# nano-esp-stm-breakout.net
KiCad netlist of a schematic drawn in EAGLE
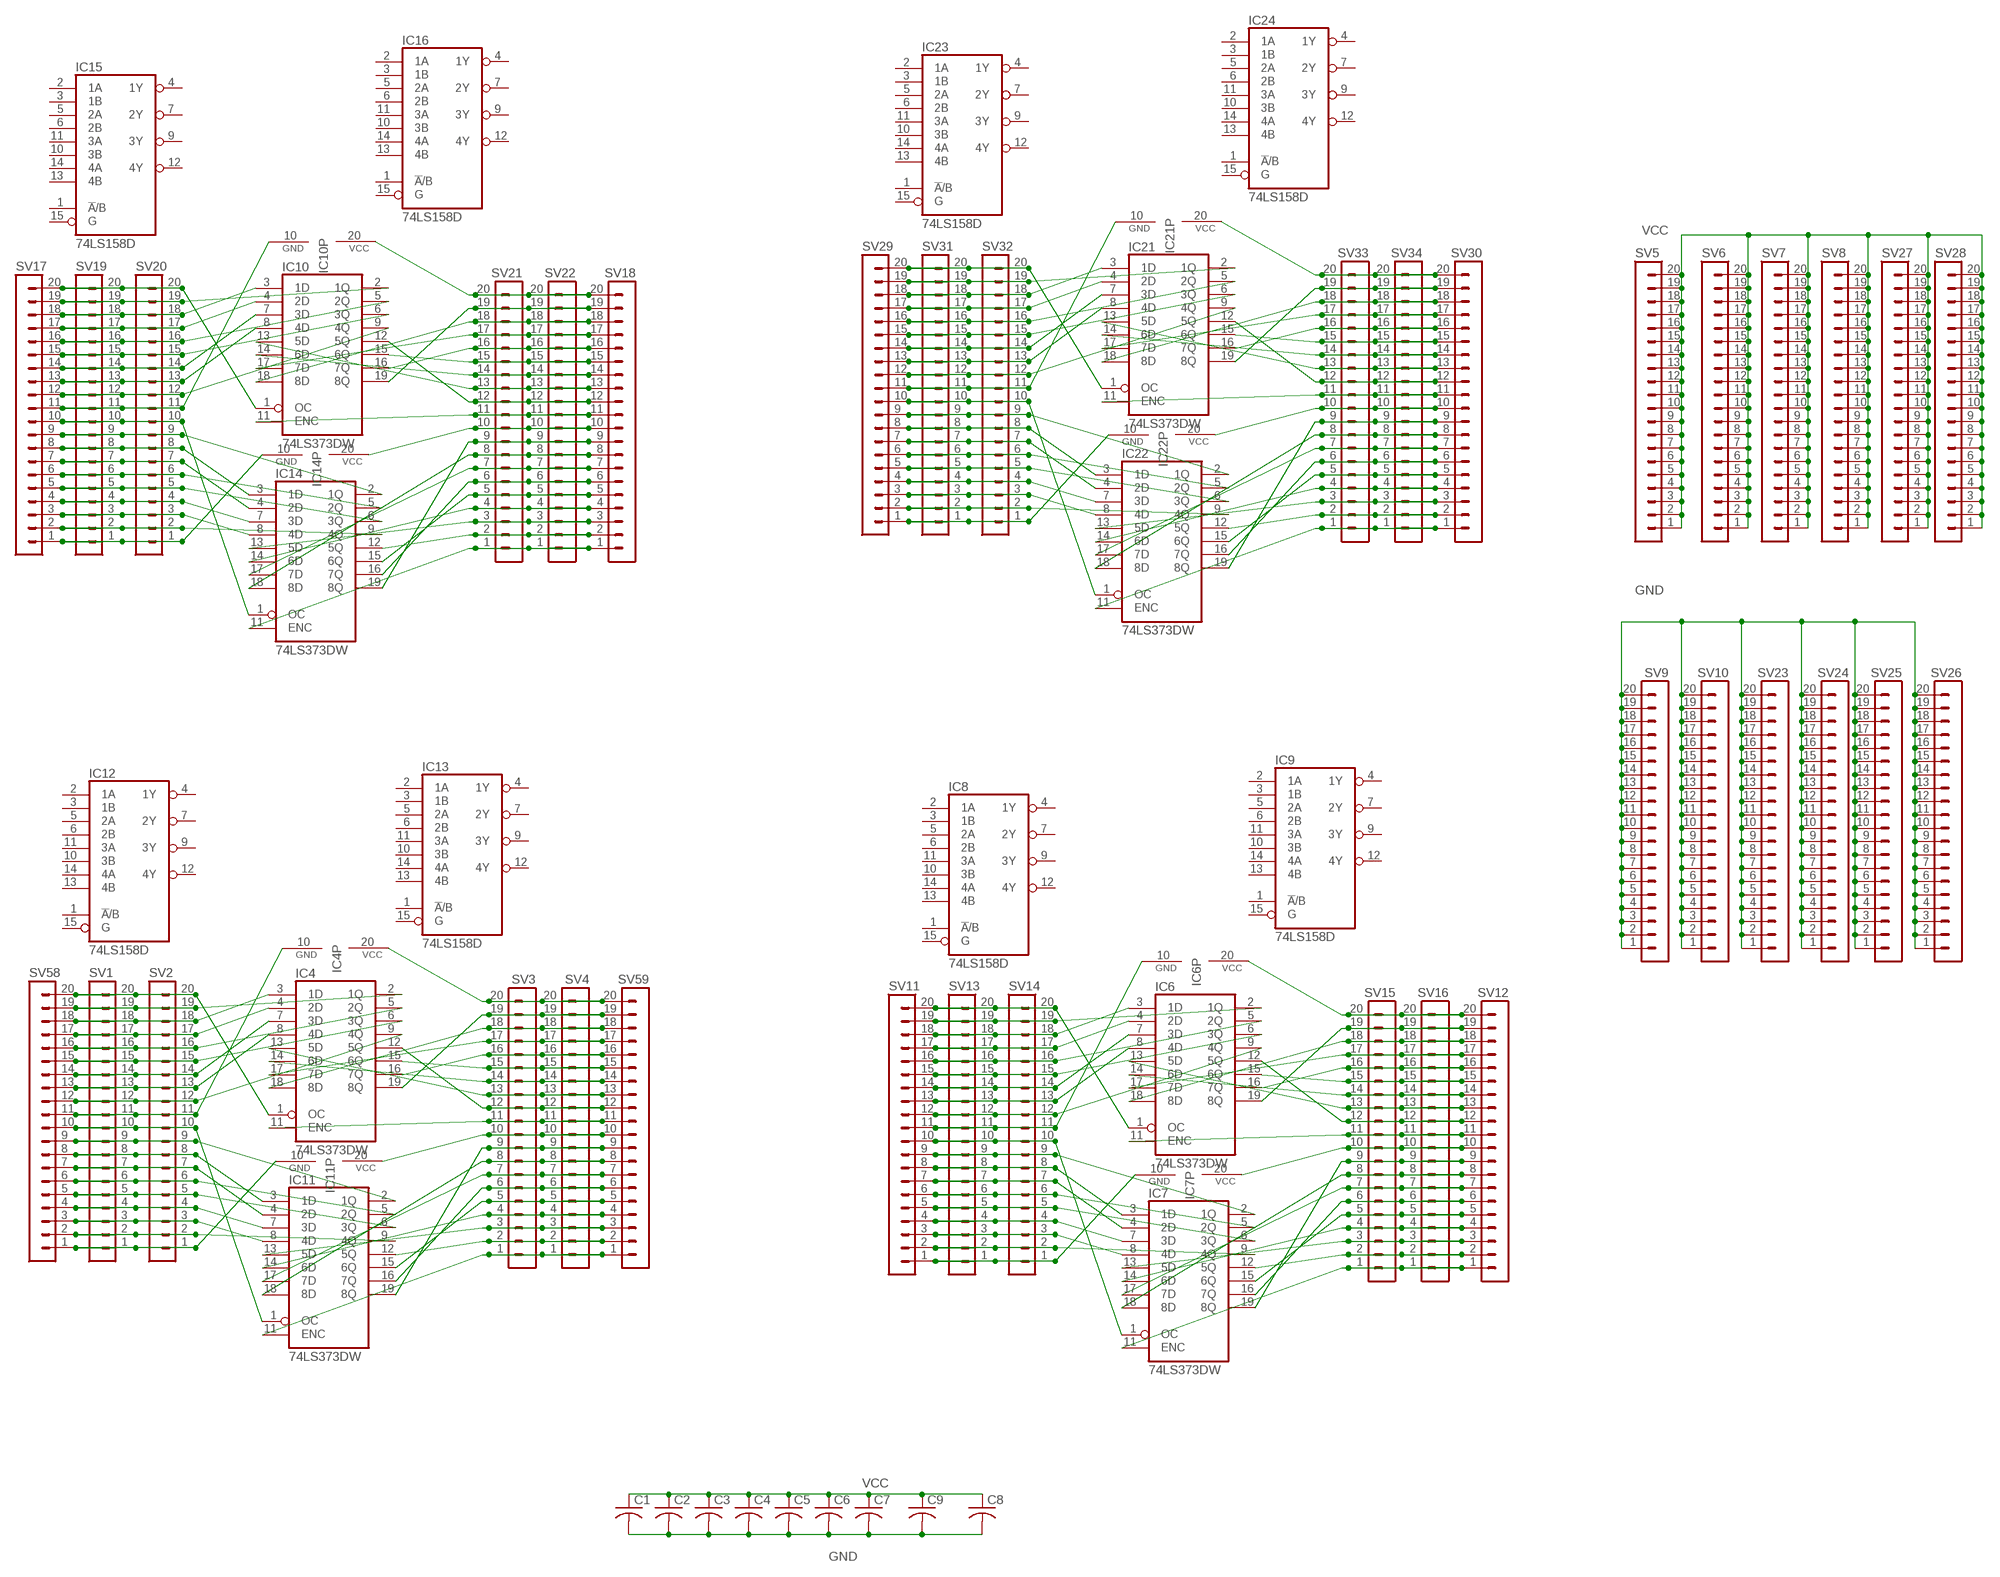
[diagram p0: schematic, sheet 1]
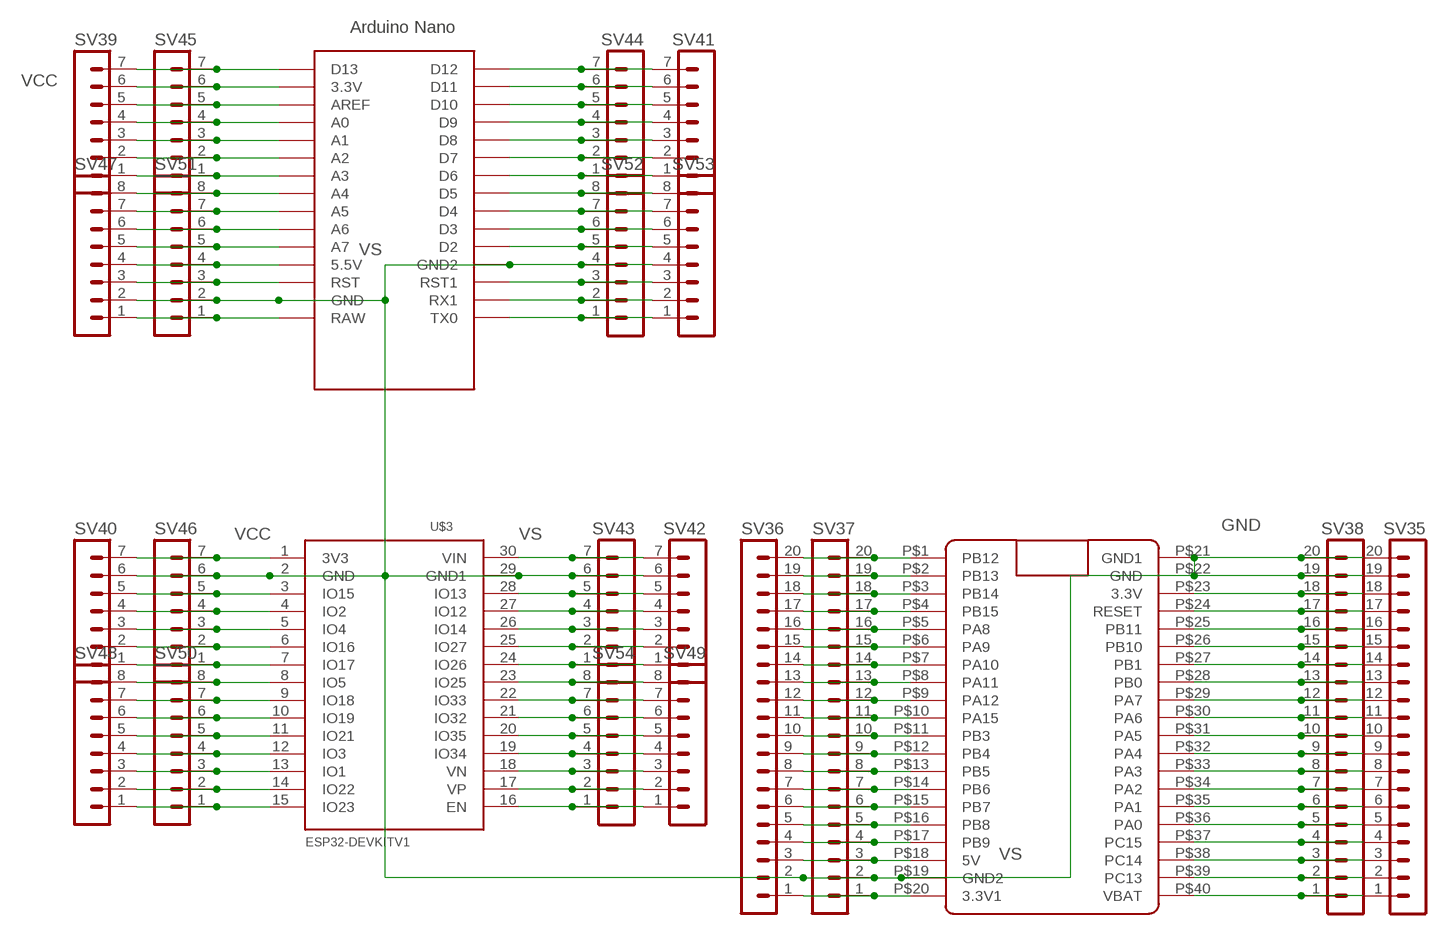
[diagram p1: schematic, sheet 2]

(export (version "E")
  (design (tool "Eeschema 10.0.6"))
  (components
    (comp (ref "C1")
      (value "C-USC0805")
      (footprint "eagle-import:C0805")
      (libsource (lib "eagle-import") (part "C-USC0805"))
    )
    (comp (ref "C2")
      (value "C-USC0805")
      (footprint "eagle-import:C0805")
      (libsource (lib "eagle-import") (part "C-USC0805"))
    )
    (comp (ref "C3")
      (value "C-USC0805")
      (footprint "eagle-import:C0805")
      (libsource (lib "eagle-import") (part "C-USC0805"))
    )
    (comp (ref "C4")
      (value "C-USC0805")
      (footprint "eagle-import:C0805")
      (libsource (lib "eagle-import") (part "C-USC0805"))
    )
    (comp (ref "C5")
      (value "C-USC0805")
      (footprint "eagle-import:C0805")
      (libsource (lib "eagle-import") (part "C-USC0805"))
    )
    (comp (ref "C6")
      (value "C-USC0805")
      (footprint "eagle-import:C0805")
      (libsource (lib "eagle-import") (part "C-USC0805"))
    )
    (comp (ref "C7")
      (value "C-USC0805")
      (footprint "eagle-import:C0805")
      (libsource (lib "eagle-import") (part "C-USC0805"))
    )
    (comp (ref "C8")
      (value "C-USC0805")
      (footprint "eagle-import:C0805")
      (libsource (lib "eagle-import") (part "C-USC0805"))
    )
    (comp (ref "C9")
      (value "C-USC0805")
      (footprint "eagle-import:C0805")
      (libsource (lib "eagle-import") (part "C-USC0805"))
    )
    (comp (ref "IC4")
      (value "74LS373DW")
      (footprint "eagle-import:SO20W")
      (libsource (lib "eagle-import") (part "74373DWLS"))
    )
    (comp (ref "IC6")
      (value "74LS373DW")
      (footprint "eagle-import:SO20W")
      (libsource (lib "eagle-import") (part "74373DWLS"))
    )
    (comp (ref "IC7")
      (value "74LS373DW")
      (footprint "eagle-import:SO20W")
      (libsource (lib "eagle-import") (part "74373DWLS"))
    )
    (comp (ref "IC8")
      (value "74LS158D")
      (footprint "eagle-import:SO16")
      (libsource (lib "eagle-import") (part "74158DLS"))
    )
    (comp (ref "IC9")
      (value "74LS158D")
      (footprint "eagle-import:SO16")
      (libsource (lib "eagle-import") (part "74158DLS"))
    )
    (comp (ref "IC10")
      (value "74LS373DW")
      (footprint "eagle-import:SO20W")
      (libsource (lib "eagle-import") (part "74373DWLS"))
    )
    (comp (ref "IC11")
      (value "74LS373DW")
      (footprint "eagle-import:SO20W")
      (libsource (lib "eagle-import") (part "74373DWLS"))
    )
    (comp (ref "IC12")
      (value "74LS158D")
      (footprint "eagle-import:SO16")
      (libsource (lib "eagle-import") (part "74158DLS"))
    )
    (comp (ref "IC13")
      (value "74LS158D")
      (footprint "eagle-import:SO16")
      (libsource (lib "eagle-import") (part "74158DLS"))
    )
    (comp (ref "IC14")
      (value "74LS373DW")
      (footprint "eagle-import:SO20W")
      (libsource (lib "eagle-import") (part "74373DWLS"))
    )
    (comp (ref "IC15")
      (value "74LS158D")
      (footprint "eagle-import:SO16")
      (libsource (lib "eagle-import") (part "74158DLS"))
    )
    (comp (ref "IC16")
      (value "74LS158D")
      (footprint "eagle-import:SO16")
      (libsource (lib "eagle-import") (part "74158DLS"))
    )
    (comp (ref "IC21")
      (value "74LS373DW")
      (footprint "eagle-import:SO20W")
      (libsource (lib "eagle-import") (part "74373DWLS"))
    )
    (comp (ref "IC22")
      (value "74LS373DW")
      (footprint "eagle-import:SO20W")
      (libsource (lib "eagle-import") (part "74373DWLS"))
    )
    (comp (ref "IC23")
      (value "74LS158D")
      (footprint "eagle-import:SO16")
      (libsource (lib "eagle-import") (part "74158DLS"))
    )
    (comp (ref "IC24")
      (value "74LS158D")
      (footprint "eagle-import:SO16")
      (libsource (lib "eagle-import") (part "74158DLS"))
    )
    (comp (ref "SV1")
      (value "MA20-1")
      (footprint "eagle-import:MA20-1")
      (libsource (lib "eagle-import") (part "MA20-1"))
    )
    (comp (ref "SV2")
      (value "MA20-1")
      (footprint "eagle-import:MA20-1")
      (libsource (lib "eagle-import") (part "MA20-1"))
    )
    (comp (ref "SV3")
      (value "MA20-1")
      (footprint "eagle-import:MA20-1")
      (libsource (lib "eagle-import") (part "MA20-1"))
    )
    (comp (ref "SV4")
      (value "MA20-1")
      (footprint "eagle-import:MA20-1")
      (libsource (lib "eagle-import") (part "MA20-1"))
    )
    (comp (ref "SV5")
      (value "MA20-1")
      (footprint "eagle-import:MA20-1")
      (libsource (lib "eagle-import") (part "MA20-1"))
    )
    (comp (ref "SV6")
      (value "MA20-1")
      (footprint "eagle-import:MA20-1")
      (libsource (lib "eagle-import") (part "MA20-1"))
    )
    (comp (ref "SV7")
      (value "MA20-1")
      (footprint "eagle-import:MA20-1")
      (libsource (lib "eagle-import") (part "MA20-1"))
    )
    (comp (ref "SV8")
      (value "MA20-1")
      (footprint "eagle-import:MA20-1")
      (libsource (lib "eagle-import") (part "MA20-1"))
    )
    (comp (ref "SV9")
      (value "MA20-1")
      (footprint "eagle-import:MA20-1")
      (libsource (lib "eagle-import") (part "MA20-1"))
    )
    (comp (ref "SV10")
      (value "MA20-1")
      (footprint "eagle-import:MA20-1")
      (libsource (lib "eagle-import") (part "MA20-1"))
    )
    (comp (ref "SV11")
      (value "MA20-1")
      (footprint "eagle-import:MA20-1")
      (libsource (lib "eagle-import") (part "MA20-1"))
    )
    (comp (ref "SV12")
      (value "MA20-1")
      (footprint "eagle-import:MA20-1")
      (libsource (lib "eagle-import") (part "MA20-1"))
    )
    (comp (ref "SV13")
      (value "MA20-1")
      (footprint "eagle-import:MA20-1")
      (libsource (lib "eagle-import") (part "MA20-1"))
    )
    (comp (ref "SV14")
      (value "MA20-1")
      (footprint "eagle-import:MA20-1")
      (libsource (lib "eagle-import") (part "MA20-1"))
    )
    (comp (ref "SV15")
      (value "MA20-1")
      (footprint "eagle-import:MA20-1")
      (libsource (lib "eagle-import") (part "MA20-1"))
    )
    (comp (ref "SV16")
      (value "MA20-1")
      (footprint "eagle-import:MA20-1")
      (libsource (lib "eagle-import") (part "MA20-1"))
    )
    (comp (ref "SV17")
      (value "MA20-1")
      (footprint "eagle-import:MA20-1")
      (libsource (lib "eagle-import") (part "MA20-1"))
    )
    (comp (ref "SV18")
      (value "MA20-1")
      (footprint "eagle-import:MA20-1")
      (libsource (lib "eagle-import") (part "MA20-1"))
    )
    (comp (ref "SV19")
      (value "MA20-1")
      (footprint "eagle-import:MA20-1")
      (libsource (lib "eagle-import") (part "MA20-1"))
    )
    (comp (ref "SV20")
      (value "MA20-1")
      (footprint "eagle-import:MA20-1")
      (libsource (lib "eagle-import") (part "MA20-1"))
    )
    (comp (ref "SV21")
      (value "MA20-1")
      (footprint "eagle-import:MA20-1")
      (libsource (lib "eagle-import") (part "MA20-1"))
    )
    (comp (ref "SV22")
      (value "MA20-1")
      (footprint "eagle-import:MA20-1")
      (libsource (lib "eagle-import") (part "MA20-1"))
    )
    (comp (ref "SV23")
      (value "MA20-1")
      (footprint "eagle-import:MA20-1")
      (libsource (lib "eagle-import") (part "MA20-1"))
    )
    (comp (ref "SV24")
      (value "MA20-1")
      (footprint "eagle-import:MA20-1")
      (libsource (lib "eagle-import") (part "MA20-1"))
    )
    (comp (ref "SV25")
      (value "MA20-1")
      (footprint "eagle-import:MA20-1")
      (libsource (lib "eagle-import") (part "MA20-1"))
    )
    (comp (ref "SV26")
      (value "MA20-1")
      (footprint "eagle-import:MA20-1")
      (libsource (lib "eagle-import") (part "MA20-1"))
    )
    (comp (ref "SV27")
      (value "MA20-1")
      (footprint "eagle-import:MA20-1")
      (libsource (lib "eagle-import") (part "MA20-1"))
    )
    (comp (ref "SV28")
      (value "MA20-1")
      (footprint "eagle-import:MA20-1")
      (libsource (lib "eagle-import") (part "MA20-1"))
    )
    (comp (ref "SV29")
      (value "MA20-1")
      (footprint "eagle-import:MA20-1")
      (libsource (lib "eagle-import") (part "MA20-1"))
    )
    (comp (ref "SV30")
      (value "MA20-1")
      (footprint "eagle-import:MA20-1")
      (libsource (lib "eagle-import") (part "MA20-1"))
    )
    (comp (ref "SV31")
      (value "MA20-1")
      (footprint "eagle-import:MA20-1")
      (libsource (lib "eagle-import") (part "MA20-1"))
    )
    (comp (ref "SV32")
      (value "MA20-1")
      (footprint "eagle-import:MA20-1")
      (libsource (lib "eagle-import") (part "MA20-1"))
    )
    (comp (ref "SV33")
      (value "MA20-1")
      (footprint "eagle-import:MA20-1")
      (libsource (lib "eagle-import") (part "MA20-1"))
    )
    (comp (ref "SV34")
      (value "MA20-1")
      (footprint "eagle-import:MA20-1")
      (libsource (lib "eagle-import") (part "MA20-1"))
    )
    (comp (ref "SV58")
      (value "MA20-1")
      (footprint "eagle-import:MA20-1")
      (libsource (lib "eagle-import") (part "MA20-1"))
    )
    (comp (ref "SV59")
      (value "MA20-1")
      (footprint "eagle-import:MA20-1")
      (libsource (lib "eagle-import") (part "MA20-1"))
    )
    (comp (ref "SV35")
      (value "MA20-1")
      (footprint "eagle-import:MA20-1")
      (libsource (lib "eagle-import") (part "MA20-1"))
    )
    (comp (ref "SV36")
      (value "MA20-1")
      (footprint "eagle-import:MA20-1")
      (libsource (lib "eagle-import") (part "MA20-1"))
    )
    (comp (ref "SV37")
      (value "MA20-1")
      (footprint "eagle-import:MA20-1")
      (libsource (lib "eagle-import") (part "MA20-1"))
    )
    (comp (ref "SV38")
      (value "MA20-1")
      (footprint "eagle-import:MA20-1")
      (libsource (lib "eagle-import") (part "MA20-1"))
    )
    (comp (ref "SV39")
      (value "MA07-1")
      (footprint "eagle-import:MA07-1")
      (libsource (lib "eagle-import") (part "MA07-1"))
    )
    (comp (ref "SV40")
      (value "MA07-1")
      (footprint "eagle-import:MA07-1")
      (libsource (lib "eagle-import") (part "MA07-1"))
    )
    (comp (ref "SV41")
      (value "MA07-1")
      (footprint "eagle-import:MA07-1")
      (libsource (lib "eagle-import") (part "MA07-1"))
    )
    (comp (ref "SV42")
      (value "MA07-1")
      (footprint "eagle-import:MA07-1")
      (libsource (lib "eagle-import") (part "MA07-1"))
    )
    (comp (ref "SV43")
      (value "MA07-1")
      (footprint "eagle-import:MA07-1")
      (libsource (lib "eagle-import") (part "MA07-1"))
    )
    (comp (ref "SV44")
      (value "MA07-1")
      (footprint "eagle-import:MA07-1")
      (libsource (lib "eagle-import") (part "MA07-1"))
    )
    (comp (ref "SV45")
      (value "MA07-1")
      (footprint "eagle-import:MA07-1")
      (libsource (lib "eagle-import") (part "MA07-1"))
    )
    (comp (ref "SV46")
      (value "MA07-1")
      (footprint "eagle-import:MA07-1")
      (libsource (lib "eagle-import") (part "MA07-1"))
    )
    (comp (ref "SV47")
      (value "MA08-1")
      (footprint "eagle-import:MA08-1")
      (libsource (lib "eagle-import") (part "MA08-1"))
    )
    (comp (ref "SV48")
      (value "MA08-1")
      (footprint "eagle-import:MA08-1")
      (libsource (lib "eagle-import") (part "MA08-1"))
    )
    (comp (ref "SV49")
      (value "MA08-1")
      (footprint "eagle-import:MA08-1")
      (libsource (lib "eagle-import") (part "MA08-1"))
    )
    (comp (ref "SV50")
      (value "MA08-1")
      (footprint "eagle-import:MA08-1")
      (libsource (lib "eagle-import") (part "MA08-1"))
    )
    (comp (ref "SV51")
      (value "MA08-1")
      (footprint "eagle-import:MA08-1")
      (libsource (lib "eagle-import") (part "MA08-1"))
    )
    (comp (ref "SV52")
      (value "MA08-1")
      (footprint "eagle-import:MA08-1")
      (libsource (lib "eagle-import") (part "MA08-1"))
    )
    (comp (ref "SV53")
      (value "MA08-1")
      (footprint "eagle-import:MA08-1")
      (libsource (lib "eagle-import") (part "MA08-1"))
    )
    (comp (ref "SV54")
      (value "MA08-1")
      (footprint "eagle-import:MA08-1")
      (libsource (lib "eagle-import") (part "MA08-1"))
    )
    (comp (ref "U$1")
      (value "NANO")
      (footprint "eagle-import:NANO")
      (libsource (lib "eagle-import") (part "NANO"))
    )
    (comp (ref "U$2")
      (value "BLUE_PILL")
      (footprint "eagle-import:BLUE_PILL")
      (libsource (lib "eagle-import") (part "BLUE_PILL"))
    )
    (comp (ref "U$3")
      (value "ESP32DEVKITV1")
      (footprint "eagle-import:ESP32-DEVKITV1")
      (libsource (lib "eagle-import") (part "ESP32DEVKITV1"))
    )
  )
  (nets
    (net (code "1") (name "GND") (class "Default")
      (node (ref "C1") (pin "2") (pinfunction "2_2") (pintype "passive"))
      (node (ref "C2") (pin "2") (pinfunction "2_2") (pintype "passive"))
      (node (ref "C3") (pin "2") (pinfunction "2_2") (pintype "passive"))
      (node (ref "C4") (pin "2") (pinfunction "2_2") (pintype "passive"))
      (node (ref "C5") (pin "2") (pinfunction "2_2") (pintype "passive"))
      (node (ref "C6") (pin "2") (pinfunction "2_2") (pintype "passive"))
      (node (ref "C7") (pin "2") (pinfunction "2_2") (pintype "passive"))
      (node (ref "C8") (pin "2") (pinfunction "2_2") (pintype "passive"))
      (node (ref "C9") (pin "2") (pinfunction "2_2") (pintype "passive"))
      (node (ref "SV10") (pin "1") (pinfunction "1_1") (pintype "passive"))
      (node (ref "SV10") (pin "10") (pinfunction "10_10") (pintype "passive"))
      (node (ref "SV10") (pin "11") (pinfunction "11_11") (pintype "passive"))
      (node (ref "SV10") (pin "12") (pinfunction "12_12") (pintype "passive"))
      (node (ref "SV10") (pin "13") (pinfunction "13_13") (pintype "passive"))
      (node (ref "SV10") (pin "14") (pinfunction "14_14") (pintype "passive"))
      (node (ref "SV10") (pin "15") (pinfunction "15_15") (pintype "passive"))
      (node (ref "SV10") (pin "16") (pinfunction "16_16") (pintype "passive"))
      (node (ref "SV10") (pin "17") (pinfunction "17_17") (pintype "passive"))
      (node (ref "SV10") (pin "18") (pinfunction "18_18") (pintype "passive"))
      (node (ref "SV10") (pin "19") (pinfunction "19_19") (pintype "passive"))
      (node (ref "SV10") (pin "2") (pinfunction "2_2") (pintype "passive"))
      (node (ref "SV10") (pin "20") (pinfunction "20_20") (pintype "passive"))
      (node (ref "SV10") (pin "3") (pinfunction "3_3") (pintype "passive"))
      (node (ref "SV10") (pin "4") (pinfunction "4_4") (pintype "passive"))
      (node (ref "SV10") (pin "5") (pinfunction "5_5") (pintype "passive"))
      (node (ref "SV10") (pin "6") (pinfunction "6_6") (pintype "passive"))
      (node (ref "SV10") (pin "7") (pinfunction "7_7") (pintype "passive"))
      (node (ref "SV10") (pin "8") (pinfunction "8_8") (pintype "passive"))
      (node (ref "SV10") (pin "9") (pinfunction "9_9") (pintype "passive"))
      (node (ref "SV23") (pin "1") (pinfunction "1_1") (pintype "passive"))
      (node (ref "SV23") (pin "10") (pinfunction "10_10") (pintype "passive"))
      (node (ref "SV23") (pin "11") (pinfunction "11_11") (pintype "passive"))
      (node (ref "SV23") (pin "12") (pinfunction "12_12") (pintype "passive"))
      (node (ref "SV23") (pin "13") (pinfunction "13_13") (pintype "passive"))
      (node (ref "SV23") (pin "14") (pinfunction "14_14") (pintype "passive"))
      (node (ref "SV23") (pin "15") (pinfunction "15_15") (pintype "passive"))
      (node (ref "SV23") (pin "16") (pinfunction "16_16") (pintype "passive"))
      (node (ref "SV23") (pin "17") (pinfunction "17_17") (pintype "passive"))
      (node (ref "SV23") (pin "18") (pinfunction "18_18") (pintype "passive"))
      (node (ref "SV23") (pin "19") (pinfunction "19_19") (pintype "passive"))
      (node (ref "SV23") (pin "2") (pinfunction "2_2") (pintype "passive"))
      (node (ref "SV23") (pin "20") (pinfunction "20_20") (pintype "passive"))
      (node (ref "SV23") (pin "3") (pinfunction "3_3") (pintype "passive"))
      (node (ref "SV23") (pin "4") (pinfunction "4_4") (pintype "passive"))
      (node (ref "SV23") (pin "5") (pinfunction "5_5") (pintype "passive"))
      (node (ref "SV23") (pin "6") (pinfunction "6_6") (pintype "passive"))
      (node (ref "SV23") (pin "7") (pinfunction "7_7") (pintype "passive"))
      (node (ref "SV23") (pin "8") (pinfunction "8_8") (pintype "passive"))
      (node (ref "SV23") (pin "9") (pinfunction "9_9") (pintype "passive"))
      (node (ref "SV24") (pin "1") (pinfunction "1_1") (pintype "passive"))
      (node (ref "SV24") (pin "10") (pinfunction "10_10") (pintype "passive"))
      (node (ref "SV24") (pin "11") (pinfunction "11_11") (pintype "passive"))
      (node (ref "SV24") (pin "12") (pinfunction "12_12") (pintype "passive"))
      (node (ref "SV24") (pin "13") (pinfunction "13_13") (pintype "passive"))
      (node (ref "SV24") (pin "14") (pinfunction "14_14") (pintype "passive"))
      (node (ref "SV24") (pin "15") (pinfunction "15_15") (pintype "passive"))
      (node (ref "SV24") (pin "16") (pinfunction "16_16") (pintype "passive"))
      (node (ref "SV24") (pin "17") (pinfunction "17_17") (pintype "passive"))
      (node (ref "SV24") (pin "18") (pinfunction "18_18") (pintype "passive"))
      (node (ref "SV24") (pin "19") (pinfunction "19_19") (pintype "passive"))
      (node (ref "SV24") (pin "2") (pinfunction "2_2") (pintype "passive"))
      (node (ref "SV24") (pin "20") (pinfunction "20_20") (pintype "passive"))
      (node (ref "SV24") (pin "3") (pinfunction "3_3") (pintype "passive"))
      (node (ref "SV24") (pin "4") (pinfunction "4_4") (pintype "passive"))
      (node (ref "SV24") (pin "5") (pinfunction "5_5") (pintype "passive"))
      (node (ref "SV24") (pin "6") (pinfunction "6_6") (pintype "passive"))
      (node (ref "SV24") (pin "7") (pinfunction "7_7") (pintype "passive"))
      (node (ref "SV24") (pin "8") (pinfunction "8_8") (pintype "passive"))
      (node (ref "SV24") (pin "9") (pinfunction "9_9") (pintype "passive"))
      (node (ref "SV25") (pin "1") (pinfunction "1_1") (pintype "passive"))
      (node (ref "SV25") (pin "10") (pinfunction "10_10") (pintype "passive"))
      (node (ref "SV25") (pin "11") (pinfunction "11_11") (pintype "passive"))
      (node (ref "SV25") (pin "12") (pinfunction "12_12") (pintype "passive"))
      (node (ref "SV25") (pin "13") (pinfunction "13_13") (pintype "passive"))
      (node (ref "SV25") (pin "14") (pinfunction "14_14") (pintype "passive"))
      (node (ref "SV25") (pin "15") (pinfunction "15_15") (pintype "passive"))
      (node (ref "SV25") (pin "16") (pinfunction "16_16") (pintype "passive"))
      (node (ref "SV25") (pin "17") (pinfunction "17_17") (pintype "passive"))
      (node (ref "SV25") (pin "18") (pinfunction "18_18") (pintype "passive"))
      (node (ref "SV25") (pin "19") (pinfunction "19_19") (pintype "passive"))
      (node (ref "SV25") (pin "2") (pinfunction "2_2") (pintype "passive"))
      (node (ref "SV25") (pin "20") (pinfunction "20_20") (pintype "passive"))
      (node (ref "SV25") (pin "3") (pinfunction "3_3") (pintype "passive"))
      (node (ref "SV25") (pin "4") (pinfunction "4_4") (pintype "passive"))
      (node (ref "SV25") (pin "5") (pinfunction "5_5") (pintype "passive"))
      (node (ref "SV25") (pin "6") (pinfunction "6_6") (pintype "passive"))
      (node (ref "SV25") (pin "7") (pinfunction "7_7") (pintype "passive"))
      (node (ref "SV25") (pin "8") (pinfunction "8_8") (pintype "passive"))
      (node (ref "SV25") (pin "9") (pinfunction "9_9") (pintype "passive"))
      (node (ref "SV26") (pin "1") (pinfunction "1_1") (pintype "passive"))
      (node (ref "SV26") (pin "10") (pinfunction "10_10") (pintype "passive"))
      (node (ref "SV26") (pin "11") (pinfunction "11_11") (pintype "passive"))
      (node (ref "SV26") (pin "12") (pinfunction "12_12") (pintype "passive"))
      (node (ref "SV26") (pin "13") (pinfunction "13_13") (pintype "passive"))
      (node (ref "SV26") (pin "14") (pinfunction "14_14") (pintype "passive"))
      (node (ref "SV26") (pin "15") (pinfunction "15_15") (pintype "passive"))
      (node (ref "SV26") (pin "16") (pinfunction "16_16") (pintype "passive"))
      (node (ref "SV26") (pin "17") (pinfunction "17_17") (pintype "passive"))
      (node (ref "SV26") (pin "18") (pinfunction "18_18") (pintype "passive"))
      (node (ref "SV26") (pin "19") (pinfunction "19_19") (pintype "passive"))
      (node (ref "SV26") (pin "2") (pinfunction "2_2") (pintype "passive"))
      (node (ref "SV26") (pin "20") (pinfunction "20_20") (pintype "passive"))
      (node (ref "SV26") (pin "3") (pinfunction "3_3") (pintype "passive"))
      (node (ref "SV26") (pin "4") (pinfunction "4_4") (pintype "passive"))
      (node (ref "SV26") (pin "5") (pinfunction "5_5") (pintype "passive"))
      (node (ref "SV26") (pin "6") (pinfunction "6_6") (pintype "passive"))
      (node (ref "SV26") (pin "7") (pinfunction "7_7") (pintype "passive"))
      (node (ref "SV26") (pin "8") (pinfunction "8_8") (pintype "passive"))
      (node (ref "SV26") (pin "9") (pinfunction "9_9") (pintype "passive"))
      (node (ref "SV35") (pin "19") (pinfunction "19_19") (pintype "passive"))
      (node (ref "SV35") (pin "20") (pinfunction "20_20") (pintype "passive"))
      (node (ref "SV36") (pin "2") (pinfunction "2_2") (pintype "passive"))
      (node (ref "SV37") (pin "2") (pinfunction "2_2") (pintype "passive"))
      (node (ref "SV38") (pin "19") (pinfunction "19_19") (pintype "passive"))
      (node (ref "SV38") (pin "20") (pinfunction "20_20") (pintype "passive"))
      (node (ref "SV40") (pin "6") (pinfunction "6_6") (pintype "passive"))
      (node (ref "SV42") (pin "6") (pinfunction "6_6") (pintype "passive"))
      (node (ref "SV43") (pin "6") (pinfunction "6_6") (pintype "passive"))
      (node (ref "SV46") (pin "6") (pinfunction "6_6") (pintype "passive"))
      (node (ref "SV47") (pin "2") (pinfunction "2_2") (pintype "passive"))
      (node (ref "SV51") (pin "2") (pinfunction "2_2") (pintype "passive"))
      (node (ref "SV52") (pin "4") (pinfunction "4_4") (pintype "passive"))
      (node (ref "SV53") (pin "4") (pinfunction "4_4") (pintype "passive"))
      (node (ref "SV9") (pin "1") (pinfunction "1_1") (pintype "passive"))
      (node (ref "SV9") (pin "10") (pinfunction "10_10") (pintype "passive"))
      (node (ref "SV9") (pin "11") (pinfunction "11_11") (pintype "passive"))
      (node (ref "SV9") (pin "12") (pinfunction "12_12") (pintype "passive"))
      (node (ref "SV9") (pin "13") (pinfunction "13_13") (pintype "passive"))
      (node (ref "SV9") (pin "14") (pinfunction "14_14") (pintype "passive"))
      (node (ref "SV9") (pin "15") (pinfunction "15_15") (pintype "passive"))
      (node (ref "SV9") (pin "16") (pinfunction "16_16") (pintype "passive"))
      (node (ref "SV9") (pin "17") (pinfunction "17_17") (pintype "passive"))
      (node (ref "SV9") (pin "18") (pinfunction "18_18") (pintype "passive"))
      (node (ref "SV9") (pin "19") (pinfunction "19_19") (pintype "passive"))
      (node (ref "SV9") (pin "2") (pinfunction "2_2") (pintype "passive"))
      (node (ref "SV9") (pin "20") (pinfunction "20_20") (pintype "passive"))
      (node (ref "SV9") (pin "3") (pinfunction "3_3") (pintype "passive"))
      (node (ref "SV9") (pin "4") (pinfunction "4_4") (pintype "passive"))
      (node (ref "SV9") (pin "5") (pinfunction "5_5") (pintype "passive"))
      (node (ref "SV9") (pin "6") (pinfunction "6_6") (pintype "passive"))
      (node (ref "SV9") (pin "7") (pinfunction "7_7") (pintype "passive"))
      (node (ref "SV9") (pin "8") (pinfunction "8_8") (pintype "passive"))
      (node (ref "SV9") (pin "9") (pinfunction "9_9") (pintype "passive"))
      (node (ref "U$1") (pin "GND") (pinfunction "GND_GND") (pintype "bidirectional"))
      (node (ref "U$1") (pin "GND1") (pinfunction "GND2_GND1") (pintype "bidirectional"))
      (node (ref "U$2") (pin "P$19") (pinfunction "GND2_P$19") (pintype "bidirectional"))
      (node (ref "U$2") (pin "P$21") (pinfunction "GND1_P$21") (pintype "power_in"))
      (node (ref "U$2") (pin "P$22") (pinfunction "GND_P$22") (pintype "bidirectional"))
      (node (ref "U$3") (pin "2") (pinfunction "GND_2") (pintype "bidirectional"))
      (node (ref "U$3") (pin "29") (pinfunction "GND1_29") (pintype "bidirectional"))
    )
    (net (code "2") (name "Net-(IC4A-1D)") (class "Default")
      (node (ref "IC4") (pin "3") (pinfunction "1D_3") (pintype "input"))
      (node (ref "SV1") (pin "18") (pinfunction "18_18") (pintype "passive"))
      (node (ref "SV2") (pin "18") (pinfunction "18_18") (pintype "passive"))
      (node (ref "SV58") (pin "18") (pinfunction "18_18") (pintype "passive"))
    )
    (net (code "3") (name "Net-(IC4A-1Q)") (class "Default")
      (node (ref "IC4") (pin "2") (pinfunction "1Q_2") (pintype "tri_state"))
      (node (ref "SV1") (pin "19") (pinfunction "19_19") (pintype "passive"))
      (node (ref "SV2") (pin "19") (pinfunction "19_19") (pintype "passive"))
      (node (ref "SV58") (pin "19") (pinfunction "19_19") (pintype "passive"))
    )
    (net (code "4") (name "Net-(IC4A-2D)") (class "Default")
      (node (ref "IC4") (pin "4") (pinfunction "2D_4") (pintype "input"))
      (node (ref "SV1") (pin "17") (pinfunction "17_17") (pintype "passive"))
      (node (ref "SV2") (pin "17") (pinfunction "17_17") (pintype "passive"))
      (node (ref "SV58") (pin "17") (pinfunction "17_17") (pintype "passive"))
    )
    (net (code "5") (name "Net-(IC4A-2Q)") (class "Default")
      (node (ref "IC4") (pin "5") (pinfunction "2Q_5") (pintype "tri_state"))
      (node (ref "SV1") (pin "16") (pinfunction "16_16") (pintype "passive"))
      (node (ref "SV2") (pin "16") (pinfunction "16_16") (pintype "passive"))
      (node (ref "SV58") (pin "16") (pinfunction "16_16") (pintype "passive"))
    )
    (net (code "6") (name "Net-(IC4A-3D)") (class "Default")
      (node (ref "IC4") (pin "7") (pinfunction "3D_7") (pintype "input"))
      (node (ref "SV1") (pin "14") (pinfunction "14_14") (pintype "passive"))
      (node (ref "SV2") (pin "14") (pinfunction "14_14") (pintype "passive"))
      (node (ref "SV58") (pin "14") (pinfunction "14_14") (pintype "passive"))
    )
    (net (code "7") (name "Net-(IC4A-3Q)") (class "Default")
      (node (ref "IC4") (pin "6") (pinfunction "3Q_6") (pintype "tri_state"))
      (node (ref "SV1") (pin "15") (pinfunction "15_15") (pintype "passive"))
      (node (ref "SV2") (pin "15") (pinfunction "15_15") (pintype "passive"))
      (node (ref "SV58") (pin "15") (pinfunction "15_15") (pintype "passive"))
    )
    (net (code "8") (name "Net-(IC4A-4D)") (class "Default")
      (node (ref "IC4") (pin "8") (pinfunction "4D_8") (pintype "input"))
      (node (ref "SV1") (pin "13") (pinfunction "13_13") (pintype "passive"))
      (node (ref "SV2") (pin "13") (pinfunction "13_13") (pintype "passive"))
      (node (ref "SV58") (pin "13") (pinfunction "13_13") (pintype "passive"))
    )
    (net (code "9") (name "Net-(IC4A-4Q)") (class "Default")
      (node (ref "IC4") (pin "9") (pinfunction "4Q_9") (pintype "tri_state"))
      (node (ref "SV1") (pin "12") (pinfunction "12_12") (pintype "passive"))
      (node (ref "SV2") (pin "12") (pinfunction "12_12") (pintype "passive"))
      (node (ref "SV58") (pin "12") (pinfunction "12_12") (pintype "passive"))
    )
    (net (code "10") (name "Net-(IC4A-5D)") (class "Default")
      (node (ref "IC4") (pin "13") (pinfunction "5D_13") (pintype "input"))
      (node (ref "SV3") (pin "13") (pinfunction "13_13") (pintype "passive"))
      (node (ref "SV4") (pin "13") (pinfunction "13_13") (pintype "passive"))
      (node (ref "SV59") (pin "13") (pinfunction "13_13") (pintype "passive"))
    )
    (net (code "11") (name "Net-(IC4A-5Q)") (class "Default")
      (node (ref "IC4") (pin "12") (pinfunction "5Q_12") (pintype "tri_state"))
      (node (ref "SV3") (pin "12") (pinfunction "12_12") (pintype "passive"))
      (node (ref "SV4") (pin "12") (pinfunction "12_12") (pintype "passive"))
      (node (ref "SV59") (pin "12") (pinfunction "12_12") (pintype "passive"))
    )
    (net (code "12") (name "Net-(IC4A-6D)") (class "Default")
      (node (ref "IC4") (pin "14") (pinfunction "6D_14") (pintype "input"))
      (node (ref "SV3") (pin "14") (pinfunction "14_14") (pintype "passive"))
      (node (ref "SV4") (pin "14") (pinfunction "14_14") (pintype "passive"))
      (node (ref "SV59") (pin "14") (pinfunction "14_14") (pintype "passive"))
    )
    (net (code "13") (name "Net-(IC4A-6Q)") (class "Default")
      (node (ref "IC4") (pin "15") (pinfunction "6Q_15") (pintype "tri_state"))
      (node (ref "SV3") (pin "15") (pinfunction "15_15") (pintype "passive"))
      (node (ref "SV4") (pin "15") (pinfunction "15_15") (pintype "passive"))
      (node (ref "SV59") (pin "15") (pinfunction "15_15") (pintype "passive"))
    )
    (net (code "14") (name "Net-(IC4A-7D)") (class "Default")
      (node (ref "IC4") (pin "17") (pinfunction "7D_17") (pintype "input"))
      (node (ref "SV3") (pin "17") (pinfunction "17_17") (pintype "passive"))
      (node (ref "SV4") (pin "17") (pinfunction "17_17") (pintype "passive"))
      (node (ref "SV59") (pin "17") (pinfunction "17_17") (pintype "passive"))
    )
    (net (code "15") (name "Net-(IC4A-7Q)") (class "Default")
      (node (ref "IC4") (pin "16") (pinfunction "7Q_16") (pintype "tri_state"))
      (node (ref "SV3") (pin "16") (pinfunction "16_16") (pintype "passive"))
      (node (ref "SV4") (pin "16") (pinfunction "16_16") (pintype "passive"))
      (node (ref "SV59") (pin "16") (pinfunction "16_16") (pintype "passive"))
    )
    (net (code "16") (name "Net-(IC4A-8D)") (class "Default")
      (node (ref "IC4") (pin "18") (pinfunction "8D_18") (pintype "input"))
      (node (ref "SV3") (pin "18") (pinfunction "18_18") (pintype "passive"))
      (node (ref "SV4") (pin "18") (pinfunction "18_18") (pintype "passive"))
      (node (ref "SV59") (pin "18") (pinfunction "18_18") (pintype "passive"))
    )
    (net (code "17") (name "Net-(IC4A-8Q)") (class "Default")
      (node (ref "IC4") (pin "19") (pinfunction "8Q_19") (pintype "tri_state"))
      (node (ref "SV3") (pin "19") (pinfunction "19_19") (pintype "passive"))
      (node (ref "SV4") (pin "19") (pinfunction "19_19") (pintype "passive"))
      (node (ref "SV59") (pin "19") (pinfunction "19_19") (pintype "passive"))
    )
    (net (code "18") (name "Net-(IC4A-ENC)") (class "Default")
      (node (ref "IC4") (pin "11") (pinfunction "ENC_11") (pintype "input"))
      (node (ref "SV3") (pin "11") (pinfunction "11_11") (pintype "passive"))
      (node (ref "SV4") (pin "11") (pinfunction "11_11") (pintype "passive"))
      (node (ref "SV59") (pin "11") (pinfunction "11_11") (pintype "passive"))
    )
    (net (code "19") (name "Net-(IC4A-OC)") (class "Default")
      (node (ref "IC4") (pin "1") (pinfunction "OC_1") (pintype "input"))
      (node (ref "SV1") (pin "20") (pinfunction "20_20") (pintype "passive"))
      (node (ref "SV2") (pin "20") (pinfunction "20_20") (pintype "passive"))
      (node (ref "SV58") (pin "20") (pinfunction "20_20") (pintype "passive"))
    )
    (net (code "20") (name "Net-(IC4B-GND)") (class "Default")
      (node (ref "IC4") (pin "10") (pinfunction "GND_10") (pintype "power_in"))
      (node (ref "SV1") (pin "11") (pinfunction "11_11") (pintype "passive"))
      (node (ref "SV2") (pin "11") (pinfunction "11_11") (pintype "passive"))
      (node (ref "SV58") (pin "11") (pinfunction "11_11") (pintype "passive"))
    )
    (net (code "21") (name "Net-(IC4B-VCC)") (class "Default")
      (node (ref "IC4") (pin "20") (pinfunction "VCC_20") (pintype "power_in"))
      (node (ref "SV3") (pin "20") (pinfunction "20_20") (pintype "passive"))
      (node (ref "SV4") (pin "20") (pinfunction "20_20") (pintype "passive"))
      (node (ref "SV59") (pin "20") (pinfunction "20_20") (pintype "passive"))
    )
    (net (code "22") (name "Net-(IC6A-1D)") (class "Default")
      (node (ref "IC6") (pin "3") (pinfunction "1D_3") (pintype "input"))
      (node (ref "SV11") (pin "18") (pinfunction "18_18") (pintype "passive"))
      (node (ref "SV13") (pin "18") (pinfunction "18_18") (pintype "passive"))
      (node (ref "SV14") (pin "18") (pinfunction "18_18") (pintype "passive"))
    )
    (net (code "23") (name "Net-(IC6A-1Q)") (class "Default")
      (node (ref "IC6") (pin "2") (pinfunction "1Q_2") (pintype "tri_state"))
      (node (ref "SV11") (pin "19") (pinfunction "19_19") (pintype "passive"))
      (node (ref "SV13") (pin "19") (pinfunction "19_19") (pintype "passive"))
      (node (ref "SV14") (pin "19") (pinfunction "19_19") (pintype "passive"))
    )
    (net (code "24") (name "Net-(IC6A-2D)") (class "Default")
      (node (ref "IC6") (pin "4") (pinfunction "2D_4") (pintype "input"))
      (node (ref "SV11") (pin "17") (pinfunction "17_17") (pintype "passive"))
      (node (ref "SV13") (pin "17") (pinfunction "17_17") (pintype "passive"))
      (node (ref "SV14") (pin "17") (pinfunction "17_17") (pintype "passive"))
    )
    (net (code "25") (name "Net-(IC6A-2Q)") (class "Default")
      (node (ref "IC6") (pin "5") (pinfunction "2Q_5") (pintype "tri_state"))
      (node (ref "SV11") (pin "16") (pinfunction "16_16") (pintype "passive"))
      (node (ref "SV13") (pin "16") (pinfunction "16_16") (pintype "passive"))
      (node (ref "SV14") (pin "16") (pinfunction "16_16") (pintype "passive"))
    )
    (net (code "26") (name "Net-(IC6A-3D)") (class "Default")
      (node (ref "IC6") (pin "7") (pinfunction "3D_7") (pintype "input"))
      (node (ref "SV11") (pin "14") (pinfunction "14_14") (pintype "passive"))
      (node (ref "SV13") (pin "14") (pinfunction "14_14") (pintype "passive"))
      (node (ref "SV14") (pin "14") (pinfunction "14_14") (pintype "passive"))
    )
    (net (code "27") (name "Net-(IC6A-3Q)") (class "Default")
      (node (ref "IC6") (pin "6") (pinfunction "3Q_6") (pintype "tri_state"))
      (node (ref "SV11") (pin "15") (pinfunction "15_15") (pintype "passive"))
      (node (ref "SV13") (pin "15") (pinfunction "15_15") (pintype "passive"))
      (node (ref "SV14") (pin "15") (pinfunction "15_15") (pintype "passive"))
    )
    (net (code "28") (name "Net-(IC6A-4D)") (class "Default")
      (node (ref "IC6") (pin "8") (pinfunction "4D_8") (pintype "input"))
      (node (ref "SV11") (pin "13") (pinfunction "13_13") (pintype "passive"))
      (node (ref "SV13") (pin "13") (pinfunction "13_13") (pintype "passive"))
      (node (ref "SV14") (pin "13") (pinfunction "13_13") (pintype "passive"))
    )
    (net (code "29") (name "Net-(IC6A-4Q)") (class "Default")
      (node (ref "IC6") (pin "9") (pinfunction "4Q_9") (pintype "tri_state"))
      (node (ref "SV11") (pin "12") (pinfunction "12_12") (pintype "passive"))
      (node (ref "SV13") (pin "12") (pinfunction "12_12") (pintype "passive"))
      (node (ref "SV14") (pin "12") (pinfunction "12_12") (pintype "passive"))
    )
    (net (code "30") (name "Net-(IC6A-5D)") (class "Default")
      (node (ref "IC6") (pin "13") (pinfunction "5D_13") (pintype "input"))
      (node (ref "SV12") (pin "13") (pinfunction "13_13") (pintype "passive"))
      (node (ref "SV15") (pin "13") (pinfunction "13_13") (pintype "passive"))
      (node (ref "SV16") (pin "13") (pinfunction "13_13") (pintype "passive"))
    )
    (net (code "31") (name "Net-(IC6A-5Q)") (class "Default")
      (node (ref "IC6") (pin "12") (pinfunction "5Q_12") (pintype "tri_state"))
      (node (ref "SV12") (pin "12") (pinfunction "12_12") (pintype "passive"))
      (node (ref "SV15") (pin "12") (pinfunction "12_12") (pintype "passive"))
      (node (ref "SV16") (pin "12") (pinfunction "12_12") (pintype "passive"))
    )
    (net (code "32") (name "Net-(IC6A-6D)") (class "Default")
      (node (ref "IC6") (pin "14") (pinfunction "6D_14") (pintype "input"))
      (node (ref "SV12") (pin "14") (pinfunction "14_14") (pintype "passive"))
      (node (ref "SV15") (pin "14") (pinfunction "14_14") (pintype "passive"))
      (node (ref "SV16") (pin "14") (pinfunction "14_14") (pintype "passive"))
    )
    (net (code "33") (name "Net-(IC6A-6Q)") (class "Default")
      (node (ref "IC6") (pin "15") (pinfunction "6Q_15") (pintype "tri_state"))
      (node (ref "SV12") (pin "15") (pinfunction "15_15") (pintype "passive"))
      (node (ref "SV15") (pin "15") (pinfunction "15_15") (pintype "passive"))
      (node (ref "SV16") (pin "15") (pinfunction "15_15") (pintype "passive"))
    )
    (net (code "34") (name "Net-(IC6A-7D)") (class "Default")
      (node (ref "IC6") (pin "17") (pinfunction "7D_17") (pintype "input"))
      (node (ref "SV12") (pin "17") (pinfunction "17_17") (pintype "passive"))
      (node (ref "SV15") (pin "17") (pinfunction "17_17") (pintype "passive"))
      (node (ref "SV16") (pin "17") (pinfunction "17_17") (pintype "passive"))
    )
    (net (code "35") (name "Net-(IC6A-7Q)") (class "Default")
      (node (ref "IC6") (pin "16") (pinfunction "7Q_16") (pintype "tri_state"))
      (node (ref "SV12") (pin "16") (pinfunction "16_16") (pintype "passive"))
      (node (ref "SV15") (pin "16") (pinfunction "16_16") (pintype "passive"))
      (node (ref "SV16") (pin "16") (pinfunction "16_16") (pintype "passive"))
    )
    (net (code "36") (name "Net-(IC6A-8D)") (class "Default")
      (node (ref "IC6") (pin "18") (pinfunction "8D_18") (pintype "input"))
      (node (ref "SV12") (pin "18") (pinfunction "18_18") (pintype "passive"))
      (node (ref "SV15") (pin "18") (pinfunction "18_18") (pintype "passive"))
      (node (ref "SV16") (pin "18") (pinfunction "18_18") (pintype "passive"))
    )
    (net (code "37") (name "Net-(IC6A-8Q)") (class "Default")
      (node (ref "IC6") (pin "19") (pinfunction "8Q_19") (pintype "tri_state"))
      (node (ref "SV12") (pin "19") (pinfunction "19_19") (pintype "passive"))
      (node (ref "SV15") (pin "19") (pinfunction "19_19") (pintype "passive"))
      (node (ref "SV16") (pin "19") (pinfunction "19_19") (pintype "passive"))
    )
    (net (code "38") (name "Net-(IC6A-ENC)") (class "Default")
      (node (ref "IC6") (pin "11") (pinfunction "ENC_11") (pintype "input"))
      (node (ref "SV12") (pin "11") (pinfunction "11_11") (pintype "passive"))
      (node (ref "SV15") (pin "11") (pinfunction "11_11") (pintype "passive"))
      (node (ref "SV16") (pin "11") (pinfunction "11_11") (pintype "passive"))
    )
    (net (code "39") (name "Net-(IC6A-OC)") (class "Default")
      (node (ref "IC6") (pin "1") (pinfunction "OC_1") (pintype "input"))
      (node (ref "SV11") (pin "20") (pinfunction "20_20") (pintype "passive"))
      (node (ref "SV13") (pin "20") (pinfunction "20_20") (pintype "passive"))
      (node (ref "SV14") (pin "20") (pinfunction "20_20") (pintype "passive"))
    )
    (net (code "40") (name "Net-(IC6B-GND)") (class "Default")
      (node (ref "IC6") (pin "10") (pinfunction "GND_10") (pintype "power_in"))
      (node (ref "SV11") (pin "11") (pinfunction "11_11") (pintype "passive"))
      (node (ref "SV13") (pin "11") (pinfunction "11_11") (pintype "passive"))
      (node (ref "SV14") (pin "11") (pinfunction "11_11") (pintype "passive"))
    )
    (net (code "41") (name "Net-(IC6B-VCC)") (class "Default")
      (node (ref "IC6") (pin "20") (pinfunction "VCC_20") (pintype "power_in"))
      (node (ref "SV12") (pin "20") (pinfunction "20_20") (pintype "passive"))
      (node (ref "SV15") (pin "20") (pinfunction "20_20") (pintype "passive"))
      (node (ref "SV16") (pin "20") (pinfunction "20_20") (pintype "passive"))
    )
    (net (code "42") (name "Net-(IC7A-1D)") (class "Default")
      (node (ref "IC7") (pin "3") (pinfunction "1D_3") (pintype "input"))
      (node (ref "SV11") (pin "8") (pinfunction "8_8") (pintype "passive"))
      (node (ref "SV13") (pin "8") (pinfunction "8_8") (pintype "passive"))
      (node (ref "SV14") (pin "8") (pinfunction "8_8") (pintype "passive"))
    )
    (net (code "43") (name "Net-(IC7A-1Q)") (class "Default")
      (node (ref "IC7") (pin "2") (pinfunction "1Q_2") (pintype "tri_state"))
      (node (ref "SV11") (pin "9") (pinfunction "9_9") (pintype "passive"))
      (node (ref "SV13") (pin "9") (pinfunction "9_9") (pintype "passive"))
      (node (ref "SV14") (pin "9") (pinfunction "9_9") (pintype "passive"))
    )
    (net (code "44") (name "Net-(IC7A-2D)") (class "Default")
      (node (ref "IC7") (pin "4") (pinfunction "2D_4") (pintype "input"))
      (node (ref "SV11") (pin "7") (pinfunction "7_7") (pintype "passive"))
      (node (ref "SV13") (pin "7") (pinfunction "7_7") (pintype "passive"))
      (node (ref "SV14") (pin "7") (pinfunction "7_7") (pintype "passive"))
    )
    (net (code "45") (name "Net-(IC7A-2Q)") (class "Default")
      (node (ref "IC7") (pin "5") (pinfunction "2Q_5") (pintype "tri_state"))
      (node (ref "SV11") (pin "6") (pinfunction "6_6") (pintype "passive"))
      (node (ref "SV13") (pin "6") (pinfunction "6_6") (pintype "passive"))
      (node (ref "SV14") (pin "6") (pinfunction "6_6") (pintype "passive"))
    )
    (net (code "46") (name "Net-(IC7A-3D)") (class "Default")
      (node (ref "IC7") (pin "7") (pinfunction "3D_7") (pintype "input"))
      (node (ref "SV11") (pin "4") (pinfunction "4_4") (pintype "passive"))
      (node (ref "SV13") (pin "4") (pinfunction "4_4") (pintype "passive"))
      (node (ref "SV14") (pin "4") (pinfunction "4_4") (pintype "passive"))
    )
    (net (code "47") (name "Net-(IC7A-3Q)") (class "Default")
      (node (ref "IC7") (pin "6") (pinfunction "3Q_6") (pintype "tri_state"))
      (node (ref "SV11") (pin "5") (pinfunction "5_5") (pintype "passive"))
      (node (ref "SV13") (pin "5") (pinfunction "5_5") (pintype "passive"))
      (node (ref "SV14") (pin "5") (pinfunction "5_5") (pintype "passive"))
    )
    (net (code "48") (name "Net-(IC7A-4D)") (class "Default")
      (node (ref "IC7") (pin "8") (pinfunction "4D_8") (pintype "input"))
      (node (ref "SV11") (pin "3") (pinfunction "3_3") (pintype "passive"))
      (node (ref "SV13") (pin "3") (pinfunction "3_3") (pintype "passive"))
      (node (ref "SV14") (pin "3") (pinfunction "3_3") (pintype "passive"))
    )
    (net (code "49") (name "Net-(IC7A-4Q)") (class "Default")
      (node (ref "IC7") (pin "9") (pinfunction "4Q_9") (pintype "tri_state"))
      (node (ref "SV11") (pin "2") (pinfunction "2_2") (pintype "passive"))
      (node (ref "SV13") (pin "2") (pinfunction "2_2") (pintype "passive"))
      (node (ref "SV14") (pin "2") (pinfunction "2_2") (pintype "passive"))
    )
    (net (code "50") (name "Net-(IC7A-5D)") (class "Default")
      (node (ref "IC7") (pin "13") (pinfunction "5D_13") (pintype "input"))
      (node (ref "SV12") (pin "3") (pinfunction "3_3") (pintype "passive"))
      (node (ref "SV15") (pin "3") (pinfunction "3_3") (pintype "passive"))
      (node (ref "SV16") (pin "3") (pinfunction "3_3") (pintype "passive"))
    )
    (net (code "51") (name "Net-(IC7A-5Q)") (class "Default")
      (node (ref "IC7") (pin "12") (pinfunction "5Q_12") (pintype "tri_state"))
      (node (ref "SV12") (pin "2") (pinfunction "2_2") (pintype "passive"))
      (node (ref "SV15") (pin "2") (pinfunction "2_2") (pintype "passive"))
      (node (ref "SV16") (pin "2") (pinfunction "2_2") (pintype "passive"))
    )
    (net (code "52") (name "Net-(IC7A-6D)") (class "Default")
      (node (ref "IC7") (pin "14") (pinfunction "6D_14") (pintype "input"))
      (node (ref "SV12") (pin "4") (pinfunction "4_4") (pintype "passive"))
      (node (ref "SV15") (pin "4") (pinfunction "4_4") (pintype "passive"))
      (node (ref "SV16") (pin "4") (pinfunction "4_4") (pintype "passive"))
    )
    (net (code "53") (name "Net-(IC7A-6Q)") (class "Default")
      (node (ref "IC7") (pin "15") (pinfunction "6Q_15") (pintype "tri_state"))
      (node (ref "SV12") (pin "5") (pinfunction "5_5") (pintype "passive"))
      (node (ref "SV15") (pin "5") (pinfunction "5_5") (pintype "passive"))
      (node (ref "SV16") (pin "5") (pinfunction "5_5") (pintype "passive"))
    )
    (net (code "54") (name "Net-(IC7A-7D)") (class "Default")
      (node (ref "IC7") (pin "17") (pinfunction "7D_17") (pintype "input"))
      (node (ref "SV12") (pin "7") (pinfunction "7_7") (pintype "passive"))
      (node (ref "SV15") (pin "7") (pinfunction "7_7") (pintype "passive"))
      (node (ref "SV16") (pin "7") (pinfunction "7_7") (pintype "passive"))
    )
    (net (code "55") (name "Net-(IC7A-7Q)") (class "Default")
      (node (ref "IC7") (pin "16") (pinfunction "7Q_16") (pintype "tri_state"))
      (node (ref "SV12") (pin "6") (pinfunction "6_6") (pintype "passive"))
      (node (ref "SV15") (pin "6") (pinfunction "6_6") (pintype "passive"))
      (node (ref "SV16") (pin "6") (pinfunction "6_6") (pintype "passive"))
    )
    (net (code "56") (name "Net-(IC7A-8D)") (class "Default")
      (node (ref "IC7") (pin "18") (pinfunction "8D_18") (pintype "input"))
      (node (ref "SV12") (pin "8") (pinfunction "8_8") (pintype "passive"))
      (node (ref "SV15") (pin "8") (pinfunction "8_8") (pintype "passive"))
      (node (ref "SV16") (pin "8") (pinfunction "8_8") (pintype "passive"))
    )
    (net (code "57") (name "Net-(IC7A-8Q)") (class "Default")
      (node (ref "IC7") (pin "19") (pinfunction "8Q_19") (pintype "tri_state"))
      (node (ref "SV12") (pin "9") (pinfunction "9_9") (pintype "passive"))
      (node (ref "SV15") (pin "9") (pinfunction "9_9") (pintype "passive"))
      (node (ref "SV16") (pin "9") (pinfunction "9_9") (pintype "passive"))
    )
    (net (code "58") (name "Net-(IC7A-ENC)") (class "Default")
      (node (ref "IC7") (pin "11") (pinfunction "ENC_11") (pintype "input"))
      (node (ref "SV12") (pin "1") (pinfunction "1_1") (pintype "passive"))
      (node (ref "SV15") (pin "1") (pinfunction "1_1") (pintype "passive"))
      (node (ref "SV16") (pin "1") (pinfunction "1_1") (pintype "passive"))
    )
    (net (code "59") (name "Net-(IC7A-OC)") (class "Default")
      (node (ref "IC7") (pin "1") (pinfunction "OC_1") (pintype "input"))
      (node (ref "SV11") (pin "10") (pinfunction "10_10") (pintype "passive"))
      (node (ref "SV13") (pin "10") (pinfunction "10_10") (pintype "passive"))
      (node (ref "SV14") (pin "10") (pinfunction "10_10") (pintype "passive"))
    )
    (net (code "60") (name "Net-(IC7B-GND)") (class "Default")
      (node (ref "IC7") (pin "10") (pinfunction "GND_10") (pintype "power_in"))
      (node (ref "SV11") (pin "1") (pinfunction "1_1") (pintype "passive"))
      (node (ref "SV13") (pin "1") (pinfunction "1_1") (pintype "passive"))
      (node (ref "SV14") (pin "1") (pinfunction "1_1") (pintype "passive"))
    )
    (net (code "61") (name "Net-(IC7B-VCC)") (class "Default")
      (node (ref "IC7") (pin "20") (pinfunction "VCC_20") (pintype "power_in"))
      (node (ref "SV12") (pin "10") (pinfunction "10_10") (pintype "passive"))
      (node (ref "SV15") (pin "10") (pinfunction "10_10") (pintype "passive"))
      (node (ref "SV16") (pin "10") (pinfunction "10_10") (pintype "passive"))
    )
    (net (code "62") (name "Net-(IC10A-1D)") (class "Default")
      (node (ref "IC10") (pin "3") (pinfunction "1D_3") (pintype "input"))
      (node (ref "SV17") (pin "18") (pinfunction "18_18") (pintype "passive"))
      (node (ref "SV19") (pin "18") (pinfunction "18_18") (pintype "passive"))
      (node (ref "SV20") (pin "18") (pinfunction "18_18") (pintype "passive"))
    )
    (net (code "63") (name "Net-(IC10A-1Q)") (class "Default")
      (node (ref "IC10") (pin "2") (pinfunction "1Q_2") (pintype "tri_state"))
      (node (ref "SV17") (pin "19") (pinfunction "19_19") (pintype "passive"))
      (node (ref "SV19") (pin "19") (pinfunction "19_19") (pintype "passive"))
      (node (ref "SV20") (pin "19") (pinfunction "19_19") (pintype "passive"))
    )
    (net (code "64") (name "Net-(IC10A-2D)") (class "Default")
      (node (ref "IC10") (pin "4") (pinfunction "2D_4") (pintype "input"))
      (node (ref "SV17") (pin "17") (pinfunction "17_17") (pintype "passive"))
      (node (ref "SV19") (pin "17") (pinfunction "17_17") (pintype "passive"))
      (node (ref "SV20") (pin "17") (pinfunction "17_17") (pintype "passive"))
    )
    (net (code "65") (name "Net-(IC10A-2Q)") (class "Default")
      (node (ref "IC10") (pin "5") (pinfunction "2Q_5") (pintype "tri_state"))
      (node (ref "SV17") (pin "16") (pinfunction "16_16") (pintype "passive"))
      (node (ref "SV19") (pin "16") (pinfunction "16_16") (pintype "passive"))
      (node (ref "SV20") (pin "16") (pinfunction "16_16") (pintype "passive"))
    )
    (net (code "66") (name "Net-(IC10A-3D)") (class "Default")
      (node (ref "IC10") (pin "7") (pinfunction "3D_7") (pintype "input"))
      (node (ref "SV17") (pin "14") (pinfunction "14_14") (pintype "passive"))
      (node (ref "SV19") (pin "14") (pinfunction "14_14") (pintype "passive"))
      (node (ref "SV20") (pin "14") (pinfunction "14_14") (pintype "passive"))
    )
    (net (code "67") (name "Net-(IC10A-3Q)") (class "Default")
      (node (ref "IC10") (pin "6") (pinfunction "3Q_6") (pintype "tri_state"))
      (node (ref "SV17") (pin "15") (pinfunction "15_15") (pintype "passive"))
      (node (ref "SV19") (pin "15") (pinfunction "15_15") (pintype "passive"))
      (node (ref "SV20") (pin "15") (pinfunction "15_15") (pintype "passive"))
    )
    (net (code "68") (name "Net-(IC10A-4D)") (class "Default")
      (node (ref "IC10") (pin "8") (pinfunction "4D_8") (pintype "input"))
      (node (ref "SV17") (pin "13") (pinfunction "13_13") (pintype "passive"))
      (node (ref "SV19") (pin "13") (pinfunction "13_13") (pintype "passive"))
      (node (ref "SV20") (pin "13") (pinfunction "13_13") (pintype "passive"))
    )
    (net (code "69") (name "Net-(IC10A-4Q)") (class "Default")
      (node (ref "IC10") (pin "9") (pinfunction "4Q_9") (pintype "tri_state"))
      (node (ref "SV17") (pin "12") (pinfunction "12_12") (pintype "passive"))
      (node (ref "SV19") (pin "12") (pinfunction "12_12") (pintype "passive"))
      (node (ref "SV20") (pin "12") (pinfunction "12_12") (pintype "passive"))
    )
    (net (code "70") (name "Net-(IC10A-5D)") (class "Default")
      (node (ref "IC10") (pin "13") (pinfunction "5D_13") (pintype "input"))
      (node (ref "SV18") (pin "13") (pinfunction "13_13") (pintype "passive"))
      (node (ref "SV21") (pin "13") (pinfunction "13_13") (pintype "passive"))
      (node (ref "SV22") (pin "13") (pinfunction "13_13") (pintype "passive"))
    )
    (net (code "71") (name "Net-(IC10A-5Q)") (class "Default")
      (node (ref "IC10") (pin "12") (pinfunction "5Q_12") (pintype "tri_state"))
      (node (ref "SV18") (pin "12") (pinfunction "12_12") (pintype "passive"))
      (node (ref "SV21") (pin "12") (pinfunction "12_12") (pintype "passive"))
      (node (ref "SV22") (pin "12") (pinfunction "12_12") (pintype "passive"))
    )
    (net (code "72") (name "Net-(IC10A-6D)") (class "Default")
      (node (ref "IC10") (pin "14") (pinfunction "6D_14") (pintype "input"))
      (node (ref "SV18") (pin "14") (pinfunction "14_14") (pintype "passive"))
      (node (ref "SV21") (pin "14") (pinfunction "14_14") (pintype "passive"))
      (node (ref "SV22") (pin "14") (pinfunction "14_14") (pintype "passive"))
    )
    (net (code "73") (name "Net-(IC10A-6Q)") (class "Default")
      (node (ref "IC10") (pin "15") (pinfunction "6Q_15") (pintype "tri_state"))
      (node (ref "SV18") (pin "15") (pinfunction "15_15") (pintype "passive"))
      (node (ref "SV21") (pin "15") (pinfunction "15_15") (pintype "passive"))
      (node (ref "SV22") (pin "15") (pinfunction "15_15") (pintype "passive"))
    )
    (net (code "74") (name "Net-(IC10A-7D)") (class "Default")
      (node (ref "IC10") (pin "17") (pinfunction "7D_17") (pintype "input"))
      (node (ref "SV18") (pin "17") (pinfunction "17_17") (pintype "passive"))
      (node (ref "SV21") (pin "17") (pinfunction "17_17") (pintype "passive"))
      (node (ref "SV22") (pin "17") (pinfunction "17_17") (pintype "passive"))
    )
    (net (code "75") (name "Net-(IC10A-7Q)") (class "Default")
      (node (ref "IC10") (pin "16") (pinfunction "7Q_16") (pintype "tri_state"))
      (node (ref "SV18") (pin "16") (pinfunction "16_16") (pintype "passive"))
      (node (ref "SV21") (pin "16") (pinfunction "16_16") (pintype "passive"))
      (node (ref "SV22") (pin "16") (pinfunction "16_16") (pintype "passive"))
    )
    (net (code "76") (name "Net-(IC10A-8D)") (class "Default")
      (node (ref "IC10") (pin "18") (pinfunction "8D_18") (pintype "input"))
      (node (ref "SV18") (pin "18") (pinfunction "18_18") (pintype "passive"))
      (node (ref "SV21") (pin "18") (pinfunction "18_18") (pintype "passive"))
      (node (ref "SV22") (pin "18") (pinfunction "18_18") (pintype "passive"))
    )
    (net (code "77") (name "Net-(IC10A-8Q)") (class "Default")
      (node (ref "IC10") (pin "19") (pinfunction "8Q_19") (pintype "tri_state"))
      (node (ref "SV18") (pin "19") (pinfunction "19_19") (pintype "passive"))
      (node (ref "SV21") (pin "19") (pinfunction "19_19") (pintype "passive"))
      (node (ref "SV22") (pin "19") (pinfunction "19_19") (pintype "passive"))
    )
    (net (code "78") (name "Net-(IC10A-ENC)") (class "Default")
      (node (ref "IC10") (pin "11") (pinfunction "ENC_11") (pintype "input"))
      (node (ref "SV18") (pin "11") (pinfunction "11_11") (pintype "passive"))
      (node (ref "SV21") (pin "11") (pinfunction "11_11") (pintype "passive"))
      (node (ref "SV22") (pin "11") (pinfunction "11_11") (pintype "passive"))
    )
    (net (code "79") (name "Net-(IC10A-OC)") (class "Default")
      (node (ref "IC10") (pin "1") (pinfunction "OC_1") (pintype "input"))
      (node (ref "SV17") (pin "20") (pinfunction "20_20") (pintype "passive"))
      (node (ref "SV19") (pin "20") (pinfunction "20_20") (pintype "passive"))
      (node (ref "SV20") (pin "20") (pinfunction "20_20") (pintype "passive"))
    )
    (net (code "80") (name "Net-(IC10B-GND)") (class "Default")
      (node (ref "IC10") (pin "10") (pinfunction "GND_10") (pintype "power_in"))
      (node (ref "SV17") (pin "11") (pinfunction "11_11") (pintype "passive"))
      (node (ref "SV19") (pin "11") (pinfunction "11_11") (pintype "passive"))
      (node (ref "SV20") (pin "11") (pinfunction "11_11") (pintype "passive"))
    )
    (net (code "81") (name "Net-(IC10B-VCC)") (class "Default")
      (node (ref "IC10") (pin "20") (pinfunction "VCC_20") (pintype "power_in"))
      (node (ref "SV18") (pin "20") (pinfunction "20_20") (pintype "passive"))
      (node (ref "SV21") (pin "20") (pinfunction "20_20") (pintype "passive"))
      (node (ref "SV22") (pin "20") (pinfunction "20_20") (pintype "passive"))
    )
    (net (code "82") (name "Net-(IC11A-1D)") (class "Default")
      (node (ref "IC11") (pin "3") (pinfunction "1D_3") (pintype "input"))
      (node (ref "SV1") (pin "8") (pinfunction "8_8") (pintype "passive"))
      (node (ref "SV2") (pin "8") (pinfunction "8_8") (pintype "passive"))
      (node (ref "SV58") (pin "8") (pinfunction "8_8") (pintype "passive"))
    )
    (net (code "83") (name "Net-(IC11A-1Q)") (class "Default")
      (node (ref "IC11") (pin "2") (pinfunction "1Q_2") (pintype "tri_state"))
      (node (ref "SV1") (pin "9") (pinfunction "9_9") (pintype "passive"))
      (node (ref "SV2") (pin "9") (pinfunction "9_9") (pintype "passive"))
      (node (ref "SV58") (pin "9") (pinfunction "9_9") (pintype "passive"))
    )
    (net (code "84") (name "Net-(IC11A-2D)") (class "Default")
      (node (ref "IC11") (pin "4") (pinfunction "2D_4") (pintype "input"))
      (node (ref "SV1") (pin "7") (pinfunction "7_7") (pintype "passive"))
      (node (ref "SV2") (pin "7") (pinfunction "7_7") (pintype "passive"))
      (node (ref "SV58") (pin "7") (pinfunction "7_7") (pintype "passive"))
    )
    (net (code "85") (name "Net-(IC11A-2Q)") (class "Default")
      (node (ref "IC11") (pin "5") (pinfunction "2Q_5") (pintype "tri_state"))
      (node (ref "SV1") (pin "6") (pinfunction "6_6") (pintype "passive"))
      (node (ref "SV2") (pin "6") (pinfunction "6_6") (pintype "passive"))
      (node (ref "SV58") (pin "6") (pinfunction "6_6") (pintype "passive"))
    )
    (net (code "86") (name "Net-(IC11A-3D)") (class "Default")
      (node (ref "IC11") (pin "7") (pinfunction "3D_7") (pintype "input"))
      (node (ref "SV1") (pin "4") (pinfunction "4_4") (pintype "passive"))
      (node (ref "SV2") (pin "4") (pinfunction "4_4") (pintype "passive"))
      (node (ref "SV58") (pin "4") (pinfunction "4_4") (pintype "passive"))
    )
    (net (code "87") (name "Net-(IC11A-3Q)") (class "Default")
      (node (ref "IC11") (pin "6") (pinfunction "3Q_6") (pintype "tri_state"))
      (node (ref "SV1") (pin "5") (pinfunction "5_5") (pintype "passive"))
      (node (ref "SV2") (pin "5") (pinfunction "5_5") (pintype "passive"))
      (node (ref "SV58") (pin "5") (pinfunction "5_5") (pintype "passive"))
    )
    (net (code "88") (name "Net-(IC11A-4D)") (class "Default")
      (node (ref "IC11") (pin "8") (pinfunction "4D_8") (pintype "input"))
      (node (ref "SV1") (pin "3") (pinfunction "3_3") (pintype "passive"))
      (node (ref "SV2") (pin "3") (pinfunction "3_3") (pintype "passive"))
      (node (ref "SV58") (pin "3") (pinfunction "3_3") (pintype "passive"))
    )
    (net (code "89") (name "Net-(IC11A-4Q)") (class "Default")
      (node (ref "IC11") (pin "9") (pinfunction "4Q_9") (pintype "tri_state"))
      (node (ref "SV1") (pin "2") (pinfunction "2_2") (pintype "passive"))
      (node (ref "SV2") (pin "2") (pinfunction "2_2") (pintype "passive"))
      (node (ref "SV58") (pin "2") (pinfunction "2_2") (pintype "passive"))
    )
    (net (code "90") (name "Net-(IC11A-5D)") (class "Default")
      (node (ref "IC11") (pin "13") (pinfunction "5D_13") (pintype "input"))
      (node (ref "SV3") (pin "3") (pinfunction "3_3") (pintype "passive"))
      (node (ref "SV4") (pin "3") (pinfunction "3_3") (pintype "passive"))
      (node (ref "SV59") (pin "3") (pinfunction "3_3") (pintype "passive"))
    )
    (net (code "91") (name "Net-(IC11A-5Q)") (class "Default")
      (node (ref "IC11") (pin "12") (pinfunction "5Q_12") (pintype "tri_state"))
      (node (ref "SV3") (pin "2") (pinfunction "2_2") (pintype "passive"))
      (node (ref "SV4") (pin "2") (pinfunction "2_2") (pintype "passive"))
      (node (ref "SV59") (pin "2") (pinfunction "2_2") (pintype "passive"))
    )
    (net (code "92") (name "Net-(IC11A-6D)") (class "Default")
      (node (ref "IC11") (pin "14") (pinfunction "6D_14") (pintype "input"))
      (node (ref "SV3") (pin "4") (pinfunction "4_4") (pintype "passive"))
      (node (ref "SV4") (pin "4") (pinfunction "4_4") (pintype "passive"))
      (node (ref "SV59") (pin "4") (pinfunction "4_4") (pintype "passive"))
    )
    (net (code "93") (name "Net-(IC11A-6Q)") (class "Default")
      (node (ref "IC11") (pin "15") (pinfunction "6Q_15") (pintype "tri_state"))
      (node (ref "SV3") (pin "5") (pinfunction "5_5") (pintype "passive"))
      (node (ref "SV4") (pin "5") (pinfunction "5_5") (pintype "passive"))
      (node (ref "SV59") (pin "5") (pinfunction "5_5") (pintype "passive"))
    )
    (net (code "94") (name "Net-(IC11A-7D)") (class "Default")
      (node (ref "IC11") (pin "17") (pinfunction "7D_17") (pintype "input"))
      (node (ref "SV3") (pin "7") (pinfunction "7_7") (pintype "passive"))
      (node (ref "SV4") (pin "7") (pinfunction "7_7") (pintype "passive"))
      (node (ref "SV59") (pin "7") (pinfunction "7_7") (pintype "passive"))
    )
    (net (code "95") (name "Net-(IC11A-7Q)") (class "Default")
      (node (ref "IC11") (pin "16") (pinfunction "7Q_16") (pintype "tri_state"))
      (node (ref "SV3") (pin "6") (pinfunction "6_6") (pintype "passive"))
      (node (ref "SV4") (pin "6") (pinfunction "6_6") (pintype "passive"))
      (node (ref "SV59") (pin "6") (pinfunction "6_6") (pintype "passive"))
    )
    (net (code "96") (name "Net-(IC11A-8D)") (class "Default")
      (node (ref "IC11") (pin "18") (pinfunction "8D_18") (pintype "input"))
      (node (ref "SV3") (pin "8") (pinfunction "8_8") (pintype "passive"))
      (node (ref "SV4") (pin "8") (pinfunction "8_8") (pintype "passive"))
      (node (ref "SV59") (pin "8") (pinfunction "8_8") (pintype "passive"))
    )
    (net (code "97") (name "Net-(IC11A-8Q)") (class "Default")
      (node (ref "IC11") (pin "19") (pinfunction "8Q_19") (pintype "tri_state"))
      (node (ref "SV3") (pin "9") (pinfunction "9_9") (pintype "passive"))
      (node (ref "SV4") (pin "9") (pinfunction "9_9") (pintype "passive"))
      (node (ref "SV59") (pin "9") (pinfunction "9_9") (pintype "passive"))
    )
    (net (code "98") (name "Net-(IC11A-ENC)") (class "Default")
      (node (ref "IC11") (pin "11") (pinfunction "ENC_11") (pintype "input"))
      (node (ref "SV3") (pin "1") (pinfunction "1_1") (pintype "passive"))
      (node (ref "SV4") (pin "1") (pinfunction "1_1") (pintype "passive"))
      (node (ref "SV59") (pin "1") (pinfunction "1_1") (pintype "passive"))
    )
    (net (code "99") (name "Net-(IC11A-OC)") (class "Default")
      (node (ref "IC11") (pin "1") (pinfunction "OC_1") (pintype "input"))
      (node (ref "SV1") (pin "10") (pinfunction "10_10") (pintype "passive"))
      (node (ref "SV2") (pin "10") (pinfunction "10_10") (pintype "passive"))
      (node (ref "SV58") (pin "10") (pinfunction "10_10") (pintype "passive"))
    )
    (net (code "100") (name "Net-(IC11B-GND)") (class "Default")
      (node (ref "IC11") (pin "10") (pinfunction "GND_10") (pintype "power_in"))
      (node (ref "SV1") (pin "1") (pinfunction "1_1") (pintype "passive"))
      (node (ref "SV2") (pin "1") (pinfunction "1_1") (pintype "passive"))
      (node (ref "SV58") (pin "1") (pinfunction "1_1") (pintype "passive"))
    )
    (net (code "101") (name "Net-(IC11B-VCC)") (class "Default")
      (node (ref "IC11") (pin "20") (pinfunction "VCC_20") (pintype "power_in"))
      (node (ref "SV3") (pin "10") (pinfunction "10_10") (pintype "passive"))
      (node (ref "SV4") (pin "10") (pinfunction "10_10") (pintype "passive"))
      (node (ref "SV59") (pin "10") (pinfunction "10_10") (pintype "passive"))
    )
    (net (code "102") (name "Net-(IC14A-1D)") (class "Default")
      (node (ref "IC14") (pin "3") (pinfunction "1D_3") (pintype "input"))
      (node (ref "SV17") (pin "8") (pinfunction "8_8") (pintype "passive"))
      (node (ref "SV19") (pin "8") (pinfunction "8_8") (pintype "passive"))
      (node (ref "SV20") (pin "8") (pinfunction "8_8") (pintype "passive"))
    )
    (net (code "103") (name "Net-(IC14A-1Q)") (class "Default")
      (node (ref "IC14") (pin "2") (pinfunction "1Q_2") (pintype "tri_state"))
      (node (ref "SV17") (pin "9") (pinfunction "9_9") (pintype "passive"))
      (node (ref "SV19") (pin "9") (pinfunction "9_9") (pintype "passive"))
      (node (ref "SV20") (pin "9") (pinfunction "9_9") (pintype "passive"))
    )
    (net (code "104") (name "Net-(IC14A-2D)") (class "Default")
      (node (ref "IC14") (pin "4") (pinfunction "2D_4") (pintype "input"))
      (node (ref "SV17") (pin "7") (pinfunction "7_7") (pintype "passive"))
      (node (ref "SV19") (pin "7") (pinfunction "7_7") (pintype "passive"))
      (node (ref "SV20") (pin "7") (pinfunction "7_7") (pintype "passive"))
    )
    (net (code "105") (name "Net-(IC14A-2Q)") (class "Default")
      (node (ref "IC14") (pin "5") (pinfunction "2Q_5") (pintype "tri_state"))
      (node (ref "SV17") (pin "6") (pinfunction "6_6") (pintype "passive"))
      (node (ref "SV19") (pin "6") (pinfunction "6_6") (pintype "passive"))
      (node (ref "SV20") (pin "6") (pinfunction "6_6") (pintype "passive"))
    )
    (net (code "106") (name "Net-(IC14A-3D)") (class "Default")
      (node (ref "IC14") (pin "7") (pinfunction "3D_7") (pintype "input"))
      (node (ref "SV17") (pin "4") (pinfunction "4_4") (pintype "passive"))
      (node (ref "SV19") (pin "4") (pinfunction "4_4") (pintype "passive"))
      (node (ref "SV20") (pin "4") (pinfunction "4_4") (pintype "passive"))
    )
    (net (code "107") (name "Net-(IC14A-3Q)") (class "Default")
      (node (ref "IC14") (pin "6") (pinfunction "3Q_6") (pintype "tri_state"))
      (node (ref "SV17") (pin "5") (pinfunction "5_5") (pintype "passive"))
      (node (ref "SV19") (pin "5") (pinfunction "5_5") (pintype "passive"))
      (node (ref "SV20") (pin "5") (pinfunction "5_5") (pintype "passive"))
    )
    (net (code "108") (name "Net-(IC14A-4D)") (class "Default")
      (node (ref "IC14") (pin "8") (pinfunction "4D_8") (pintype "input"))
      (node (ref "SV17") (pin "3") (pinfunction "3_3") (pintype "passive"))
      (node (ref "SV19") (pin "3") (pinfunction "3_3") (pintype "passive"))
      (node (ref "SV20") (pin "3") (pinfunction "3_3") (pintype "passive"))
    )
    (net (code "109") (name "Net-(IC14A-4Q)") (class "Default")
      (node (ref "IC14") (pin "9") (pinfunction "4Q_9") (pintype "tri_state"))
      (node (ref "SV17") (pin "2") (pinfunction "2_2") (pintype "passive"))
      (node (ref "SV19") (pin "2") (pinfunction "2_2") (pintype "passive"))
      (node (ref "SV20") (pin "2") (pinfunction "2_2") (pintype "passive"))
    )
    (net (code "110") (name "Net-(IC14A-5D)") (class "Default")
      (node (ref "IC14") (pin "13") (pinfunction "5D_13") (pintype "input"))
      (node (ref "SV18") (pin "3") (pinfunction "3_3") (pintype "passive"))
      (node (ref "SV21") (pin "3") (pinfunction "3_3") (pintype "passive"))
      (node (ref "SV22") (pin "3") (pinfunction "3_3") (pintype "passive"))
    )
    (net (code "111") (name "Net-(IC14A-5Q)") (class "Default")
      (node (ref "IC14") (pin "12") (pinfunction "5Q_12") (pintype "tri_state"))
      (node (ref "SV18") (pin "2") (pinfunction "2_2") (pintype "passive"))
      (node (ref "SV21") (pin "2") (pinfunction "2_2") (pintype "passive"))
      (node (ref "SV22") (pin "2") (pinfunction "2_2") (pintype "passive"))
    )
    (net (code "112") (name "Net-(IC14A-6D)") (class "Default")
      (node (ref "IC14") (pin "14") (pinfunction "6D_14") (pintype "input"))
      (node (ref "SV18") (pin "4") (pinfunction "4_4") (pintype "passive"))
      (node (ref "SV21") (pin "4") (pinfunction "4_4") (pintype "passive"))
      (node (ref "SV22") (pin "4") (pinfunction "4_4") (pintype "passive"))
    )
    (net (code "113") (name "Net-(IC14A-6Q)") (class "Default")
      (node (ref "IC14") (pin "15") (pinfunction "6Q_15") (pintype "tri_state"))
      (node (ref "SV18") (pin "5") (pinfunction "5_5") (pintype "passive"))
      (node (ref "SV21") (pin "5") (pinfunction "5_5") (pintype "passive"))
      (node (ref "SV22") (pin "5") (pinfunction "5_5") (pintype "passive"))
    )
    (net (code "114") (name "Net-(IC14A-7D)") (class "Default")
      (node (ref "IC14") (pin "17") (pinfunction "7D_17") (pintype "input"))
      (node (ref "SV18") (pin "7") (pinfunction "7_7") (pintype "passive"))
      (node (ref "SV21") (pin "7") (pinfunction "7_7") (pintype "passive"))
      (node (ref "SV22") (pin "7") (pinfunction "7_7") (pintype "passive"))
    )
    (net (code "115") (name "Net-(IC14A-7Q)") (class "Default")
      (node (ref "IC14") (pin "16") (pinfunction "7Q_16") (pintype "tri_state"))
      (node (ref "SV18") (pin "6") (pinfunction "6_6") (pintype "passive"))
      (node (ref "SV21") (pin "6") (pinfunction "6_6") (pintype "passive"))
      (node (ref "SV22") (pin "6") (pinfunction "6_6") (pintype "passive"))
    )
    (net (code "116") (name "Net-(IC14A-8D)") (class "Default")
      (node (ref "IC14") (pin "18") (pinfunction "8D_18") (pintype "input"))
      (node (ref "SV18") (pin "8") (pinfunction "8_8") (pintype "passive"))
      (node (ref "SV21") (pin "8") (pinfunction "8_8") (pintype "passive"))
      (node (ref "SV22") (pin "8") (pinfunction "8_8") (pintype "passive"))
    )
    (net (code "117") (name "Net-(IC14A-8Q)") (class "Default")
      (node (ref "IC14") (pin "19") (pinfunction "8Q_19") (pintype "tri_state"))
      (node (ref "SV18") (pin "9") (pinfunction "9_9") (pintype "passive"))
      (node (ref "SV21") (pin "9") (pinfunction "9_9") (pintype "passive"))
      (node (ref "SV22") (pin "9") (pinfunction "9_9") (pintype "passive"))
    )
    (net (code "118") (name "Net-(IC14A-ENC)") (class "Default")
      (node (ref "IC14") (pin "11") (pinfunction "ENC_11") (pintype "input"))
      (node (ref "SV18") (pin "1") (pinfunction "1_1") (pintype "passive"))
      (node (ref "SV21") (pin "1") (pinfunction "1_1") (pintype "passive"))
      (node (ref "SV22") (pin "1") (pinfunction "1_1") (pintype "passive"))
    )
    (net (code "119") (name "Net-(IC14A-OC)") (class "Default")
      (node (ref "IC14") (pin "1") (pinfunction "OC_1") (pintype "input"))
      (node (ref "SV17") (pin "10") (pinfunction "10_10") (pintype "passive"))
      (node (ref "SV19") (pin "10") (pinfunction "10_10") (pintype "passive"))
      (node (ref "SV20") (pin "10") (pinfunction "10_10") (pintype "passive"))
    )
    (net (code "120") (name "Net-(IC14B-GND)") (class "Default")
      (node (ref "IC14") (pin "10") (pinfunction "GND_10") (pintype "power_in"))
      (node (ref "SV17") (pin "1") (pinfunction "1_1") (pintype "passive"))
      (node (ref "SV19") (pin "1") (pinfunction "1_1") (pintype "passive"))
      (node (ref "SV20") (pin "1") (pinfunction "1_1") (pintype "passive"))
    )
    (net (code "121") (name "Net-(IC14B-VCC)") (class "Default")
      (node (ref "IC14") (pin "20") (pinfunction "VCC_20") (pintype "power_in"))
      (node (ref "SV18") (pin "10") (pinfunction "10_10") (pintype "passive"))
      (node (ref "SV21") (pin "10") (pinfunction "10_10") (pintype "passive"))
      (node (ref "SV22") (pin "10") (pinfunction "10_10") (pintype "passive"))
    )
    (net (code "122") (name "Net-(IC21A-1D)") (class "Default")
      (node (ref "IC21") (pin "3") (pinfunction "1D_3") (pintype "input"))
      (node (ref "SV29") (pin "18") (pinfunction "18_18") (pintype "passive"))
      (node (ref "SV31") (pin "18") (pinfunction "18_18") (pintype "passive"))
      (node (ref "SV32") (pin "18") (pinfunction "18_18") (pintype "passive"))
    )
    (net (code "123") (name "Net-(IC21A-1Q)") (class "Default")
      (node (ref "IC21") (pin "2") (pinfunction "1Q_2") (pintype "tri_state"))
      (node (ref "SV29") (pin "19") (pinfunction "19_19") (pintype "passive"))
      (node (ref "SV31") (pin "19") (pinfunction "19_19") (pintype "passive"))
      (node (ref "SV32") (pin "19") (pinfunction "19_19") (pintype "passive"))
    )
    (net (code "124") (name "Net-(IC21A-2D)") (class "Default")
      (node (ref "IC21") (pin "4") (pinfunction "2D_4") (pintype "input"))
      (node (ref "SV29") (pin "17") (pinfunction "17_17") (pintype "passive"))
      (node (ref "SV31") (pin "17") (pinfunction "17_17") (pintype "passive"))
      (node (ref "SV32") (pin "17") (pinfunction "17_17") (pintype "passive"))
    )
    (net (code "125") (name "Net-(IC21A-2Q)") (class "Default")
      (node (ref "IC21") (pin "5") (pinfunction "2Q_5") (pintype "tri_state"))
      (node (ref "SV29") (pin "16") (pinfunction "16_16") (pintype "passive"))
      (node (ref "SV31") (pin "16") (pinfunction "16_16") (pintype "passive"))
      (node (ref "SV32") (pin "16") (pinfunction "16_16") (pintype "passive"))
    )
    (net (code "126") (name "Net-(IC21A-3D)") (class "Default")
      (node (ref "IC21") (pin "7") (pinfunction "3D_7") (pintype "input"))
      (node (ref "SV29") (pin "14") (pinfunction "14_14") (pintype "passive"))
      (node (ref "SV31") (pin "14") (pinfunction "14_14") (pintype "passive"))
      (node (ref "SV32") (pin "14") (pinfunction "14_14") (pintype "passive"))
    )
    (net (code "127") (name "Net-(IC21A-3Q)") (class "Default")
      (node (ref "IC21") (pin "6") (pinfunction "3Q_6") (pintype "tri_state"))
      (node (ref "SV29") (pin "15") (pinfunction "15_15") (pintype "passive"))
      (node (ref "SV31") (pin "15") (pinfunction "15_15") (pintype "passive"))
      (node (ref "SV32") (pin "15") (pinfunction "15_15") (pintype "passive"))
    )
    (net (code "128") (name "Net-(IC21A-4D)") (class "Default")
      (node (ref "IC21") (pin "8") (pinfunction "4D_8") (pintype "input"))
      (node (ref "SV29") (pin "13") (pinfunction "13_13") (pintype "passive"))
      (node (ref "SV31") (pin "13") (pinfunction "13_13") (pintype "passive"))
      (node (ref "SV32") (pin "13") (pinfunction "13_13") (pintype "passive"))
    )
    (net (code "129") (name "Net-(IC21A-4Q)") (class "Default")
      (node (ref "IC21") (pin "9") (pinfunction "4Q_9") (pintype "tri_state"))
      (node (ref "SV29") (pin "12") (pinfunction "12_12") (pintype "passive"))
      (node (ref "SV31") (pin "12") (pinfunction "12_12") (pintype "passive"))
      (node (ref "SV32") (pin "12") (pinfunction "12_12") (pintype "passive"))
    )
    (net (code "130") (name "Net-(IC21A-5D)") (class "Default")
      (node (ref "IC21") (pin "13") (pinfunction "5D_13") (pintype "input"))
      (node (ref "SV30") (pin "13") (pinfunction "13_13") (pintype "passive"))
      (node (ref "SV33") (pin "13") (pinfunction "13_13") (pintype "passive"))
      (node (ref "SV34") (pin "13") (pinfunction "13_13") (pintype "passive"))
    )
    (net (code "131") (name "Net-(IC21A-5Q)") (class "Default")
      (node (ref "IC21") (pin "12") (pinfunction "5Q_12") (pintype "tri_state"))
      (node (ref "SV30") (pin "12") (pinfunction "12_12") (pintype "passive"))
      (node (ref "SV33") (pin "12") (pinfunction "12_12") (pintype "passive"))
      (node (ref "SV34") (pin "12") (pinfunction "12_12") (pintype "passive"))
    )
    (net (code "132") (name "Net-(IC21A-6D)") (class "Default")
      (node (ref "IC21") (pin "14") (pinfunction "6D_14") (pintype "input"))
      (node (ref "SV30") (pin "14") (pinfunction "14_14") (pintype "passive"))
      (node (ref "SV33") (pin "14") (pinfunction "14_14") (pintype "passive"))
      (node (ref "SV34") (pin "14") (pinfunction "14_14") (pintype "passive"))
    )
    (net (code "133") (name "Net-(IC21A-6Q)") (class "Default")
      (node (ref "IC21") (pin "15") (pinfunction "6Q_15") (pintype "tri_state"))
      (node (ref "SV30") (pin "15") (pinfunction "15_15") (pintype "passive"))
      (node (ref "SV33") (pin "15") (pinfunction "15_15") (pintype "passive"))
      (node (ref "SV34") (pin "15") (pinfunction "15_15") (pintype "passive"))
    )
    (net (code "134") (name "Net-(IC21A-7D)") (class "Default")
      (node (ref "IC21") (pin "17") (pinfunction "7D_17") (pintype "input"))
      (node (ref "SV30") (pin "17") (pinfunction "17_17") (pintype "passive"))
      (node (ref "SV33") (pin "17") (pinfunction "17_17") (pintype "passive"))
      (node (ref "SV34") (pin "17") (pinfunction "17_17") (pintype "passive"))
    )
    (net (code "135") (name "Net-(IC21A-7Q)") (class "Default")
      (node (ref "IC21") (pin "16") (pinfunction "7Q_16") (pintype "tri_state"))
      (node (ref "SV30") (pin "16") (pinfunction "16_16") (pintype "passive"))
      (node (ref "SV33") (pin "16") (pinfunction "16_16") (pintype "passive"))
      (node (ref "SV34") (pin "16") (pinfunction "16_16") (pintype "passive"))
    )
    (net (code "136") (name "Net-(IC21A-8D)") (class "Default")
      (node (ref "IC21") (pin "18") (pinfunction "8D_18") (pintype "input"))
      (node (ref "SV30") (pin "18") (pinfunction "18_18") (pintype "passive"))
      (node (ref "SV33") (pin "18") (pinfunction "18_18") (pintype "passive"))
      (node (ref "SV34") (pin "18") (pinfunction "18_18") (pintype "passive"))
    )
    (net (code "137") (name "Net-(IC21A-8Q)") (class "Default")
      (node (ref "IC21") (pin "19") (pinfunction "8Q_19") (pintype "tri_state"))
      (node (ref "SV30") (pin "19") (pinfunction "19_19") (pintype "passive"))
      (node (ref "SV33") (pin "19") (pinfunction "19_19") (pintype "passive"))
      (node (ref "SV34") (pin "19") (pinfunction "19_19") (pintype "passive"))
    )
    (net (code "138") (name "Net-(IC21A-ENC)") (class "Default")
      (node (ref "IC21") (pin "11") (pinfunction "ENC_11") (pintype "input"))
      (node (ref "SV30") (pin "11") (pinfunction "11_11") (pintype "passive"))
      (node (ref "SV33") (pin "11") (pinfunction "11_11") (pintype "passive"))
      (node (ref "SV34") (pin "11") (pinfunction "11_11") (pintype "passive"))
    )
    (net (code "139") (name "Net-(IC21A-OC)") (class "Default")
      (node (ref "IC21") (pin "1") (pinfunction "OC_1") (pintype "input"))
      (node (ref "SV29") (pin "20") (pinfunction "20_20") (pintype "passive"))
      (node (ref "SV31") (pin "20") (pinfunction "20_20") (pintype "passive"))
      (node (ref "SV32") (pin "20") (pinfunction "20_20") (pintype "passive"))
    )
    (net (code "140") (name "Net-(IC21B-GND)") (class "Default")
      (node (ref "IC21") (pin "10") (pinfunction "GND_10") (pintype "power_in"))
      (node (ref "SV29") (pin "11") (pinfunction "11_11") (pintype "passive"))
      (node (ref "SV31") (pin "11") (pinfunction "11_11") (pintype "passive"))
      (node (ref "SV32") (pin "11") (pinfunction "11_11") (pintype "passive"))
    )
    (net (code "141") (name "Net-(IC21B-VCC)") (class "Default")
      (node (ref "IC21") (pin "20") (pinfunction "VCC_20") (pintype "power_in"))
      (node (ref "SV30") (pin "20") (pinfunction "20_20") (pintype "passive"))
      (node (ref "SV33") (pin "20") (pinfunction "20_20") (pintype "passive"))
      (node (ref "SV34") (pin "20") (pinfunction "20_20") (pintype "passive"))
    )
    (net (code "142") (name "Net-(IC22A-1D)") (class "Default")
      (node (ref "IC22") (pin "3") (pinfunction "1D_3") (pintype "input"))
      (node (ref "SV29") (pin "8") (pinfunction "8_8") (pintype "passive"))
      (node (ref "SV31") (pin "8") (pinfunction "8_8") (pintype "passive"))
      (node (ref "SV32") (pin "8") (pinfunction "8_8") (pintype "passive"))
    )
    (net (code "143") (name "Net-(IC22A-1Q)") (class "Default")
      (node (ref "IC22") (pin "2") (pinfunction "1Q_2") (pintype "tri_state"))
      (node (ref "SV29") (pin "9") (pinfunction "9_9") (pintype "passive"))
      (node (ref "SV31") (pin "9") (pinfunction "9_9") (pintype "passive"))
      (node (ref "SV32") (pin "9") (pinfunction "9_9") (pintype "passive"))
    )
    (net (code "144") (name "Net-(IC22A-2D)") (class "Default")
      (node (ref "IC22") (pin "4") (pinfunction "2D_4") (pintype "input"))
      (node (ref "SV29") (pin "7") (pinfunction "7_7") (pintype "passive"))
      (node (ref "SV31") (pin "7") (pinfunction "7_7") (pintype "passive"))
      (node (ref "SV32") (pin "7") (pinfunction "7_7") (pintype "passive"))
    )
    (net (code "145") (name "Net-(IC22A-2Q)") (class "Default")
      (node (ref "IC22") (pin "5") (pinfunction "2Q_5") (pintype "tri_state"))
      (node (ref "SV29") (pin "6") (pinfunction "6_6") (pintype "passive"))
      (node (ref "SV31") (pin "6") (pinfunction "6_6") (pintype "passive"))
      (node (ref "SV32") (pin "6") (pinfunction "6_6") (pintype "passive"))
    )
    (net (code "146") (name "Net-(IC22A-3D)") (class "Default")
      (node (ref "IC22") (pin "7") (pinfunction "3D_7") (pintype "input"))
      (node (ref "SV29") (pin "4") (pinfunction "4_4") (pintype "passive"))
      (node (ref "SV31") (pin "4") (pinfunction "4_4") (pintype "passive"))
      (node (ref "SV32") (pin "4") (pinfunction "4_4") (pintype "passive"))
    )
    (net (code "147") (name "Net-(IC22A-3Q)") (class "Default")
      (node (ref "IC22") (pin "6") (pinfunction "3Q_6") (pintype "tri_state"))
      (node (ref "SV29") (pin "5") (pinfunction "5_5") (pintype "passive"))
      (node (ref "SV31") (pin "5") (pinfunction "5_5") (pintype "passive"))
      (node (ref "SV32") (pin "5") (pinfunction "5_5") (pintype "passive"))
    )
    (net (code "148") (name "Net-(IC22A-4D)") (class "Default")
      (node (ref "IC22") (pin "8") (pinfunction "4D_8") (pintype "input"))
      (node (ref "SV29") (pin "3") (pinfunction "3_3") (pintype "passive"))
      (node (ref "SV31") (pin "3") (pinfunction "3_3") (pintype "passive"))
      (node (ref "SV32") (pin "3") (pinfunction "3_3") (pintype "passive"))
    )
    (net (code "149") (name "Net-(IC22A-4Q)") (class "Default")
      (node (ref "IC22") (pin "9") (pinfunction "4Q_9") (pintype "tri_state"))
      (node (ref "SV29") (pin "2") (pinfunction "2_2") (pintype "passive"))
      (node (ref "SV31") (pin "2") (pinfunction "2_2") (pintype "passive"))
      (node (ref "SV32") (pin "2") (pinfunction "2_2") (pintype "passive"))
    )
    (net (code "150") (name "Net-(IC22A-5D)") (class "Default")
      (node (ref "IC22") (pin "13") (pinfunction "5D_13") (pintype "input"))
      (node (ref "SV30") (pin "3") (pinfunction "3_3") (pintype "passive"))
      (node (ref "SV33") (pin "3") (pinfunction "3_3") (pintype "passive"))
      (node (ref "SV34") (pin "3") (pinfunction "3_3") (pintype "passive"))
    )
    (net (code "151") (name "Net-(IC22A-5Q)") (class "Default")
      (node (ref "IC22") (pin "12") (pinfunction "5Q_12") (pintype "tri_state"))
      (node (ref "SV30") (pin "2") (pinfunction "2_2") (pintype "passive"))
      (node (ref "SV33") (pin "2") (pinfunction "2_2") (pintype "passive"))
      (node (ref "SV34") (pin "2") (pinfunction "2_2") (pintype "passive"))
    )
    (net (code "152") (name "Net-(IC22A-6D)") (class "Default")
      (node (ref "IC22") (pin "14") (pinfunction "6D_14") (pintype "input"))
      (node (ref "SV30") (pin "4") (pinfunction "4_4") (pintype "passive"))
      (node (ref "SV33") (pin "4") (pinfunction "4_4") (pintype "passive"))
      (node (ref "SV34") (pin "4") (pinfunction "4_4") (pintype "passive"))
    )
    (net (code "153") (name "Net-(IC22A-6Q)") (class "Default")
      (node (ref "IC22") (pin "15") (pinfunction "6Q_15") (pintype "tri_state"))
      (node (ref "SV30") (pin "5") (pinfunction "5_5") (pintype "passive"))
      (node (ref "SV33") (pin "5") (pinfunction "5_5") (pintype "passive"))
      (node (ref "SV34") (pin "5") (pinfunction "5_5") (pintype "passive"))
    )
    (net (code "154") (name "Net-(IC22A-7D)") (class "Default")
      (node (ref "IC22") (pin "17") (pinfunction "7D_17") (pintype "input"))
      (node (ref "SV30") (pin "7") (pinfunction "7_7") (pintype "passive"))
      (node (ref "SV33") (pin "7") (pinfunction "7_7") (pintype "passive"))
      (node (ref "SV34") (pin "7") (pinfunction "7_7") (pintype "passive"))
    )
    (net (code "155") (name "Net-(IC22A-7Q)") (class "Default")
      (node (ref "IC22") (pin "16") (pinfunction "7Q_16") (pintype "tri_state"))
      (node (ref "SV30") (pin "6") (pinfunction "6_6") (pintype "passive"))
      (node (ref "SV33") (pin "6") (pinfunction "6_6") (pintype "passive"))
      (node (ref "SV34") (pin "6") (pinfunction "6_6") (pintype "passive"))
    )
    (net (code "156") (name "Net-(IC22A-8D)") (class "Default")
      (node (ref "IC22") (pin "18") (pinfunction "8D_18") (pintype "input"))
      (node (ref "SV30") (pin "8") (pinfunction "8_8") (pintype "passive"))
      (node (ref "SV33") (pin "8") (pinfunction "8_8") (pintype "passive"))
      (node (ref "SV34") (pin "8") (pinfunction "8_8") (pintype "passive"))
    )
    (net (code "157") (name "Net-(IC22A-8Q)") (class "Default")
      (node (ref "IC22") (pin "19") (pinfunction "8Q_19") (pintype "tri_state"))
      (node (ref "SV30") (pin "9") (pinfunction "9_9") (pintype "passive"))
      (node (ref "SV33") (pin "9") (pinfunction "9_9") (pintype "passive"))
      (node (ref "SV34") (pin "9") (pinfunction "9_9") (pintype "passive"))
    )
    (net (code "158") (name "Net-(IC22A-ENC)") (class "Default")
      (node (ref "IC22") (pin "11") (pinfunction "ENC_11") (pintype "input"))
      (node (ref "SV30") (pin "1") (pinfunction "1_1") (pintype "passive"))
      (node (ref "SV33") (pin "1") (pinfunction "1_1") (pintype "passive"))
      (node (ref "SV34") (pin "1") (pinfunction "1_1") (pintype "passive"))
    )
    (net (code "159") (name "Net-(IC22A-OC)") (class "Default")
      (node (ref "IC22") (pin "1") (pinfunction "OC_1") (pintype "input"))
      (node (ref "SV29") (pin "10") (pinfunction "10_10") (pintype "passive"))
      (node (ref "SV31") (pin "10") (pinfunction "10_10") (pintype "passive"))
      (node (ref "SV32") (pin "10") (pinfunction "10_10") (pintype "passive"))
    )
    (net (code "160") (name "Net-(IC22B-GND)") (class "Default")
      (node (ref "IC22") (pin "10") (pinfunction "GND_10") (pintype "power_in"))
      (node (ref "SV29") (pin "1") (pinfunction "1_1") (pintype "passive"))
      (node (ref "SV31") (pin "1") (pinfunction "1_1") (pintype "passive"))
      (node (ref "SV32") (pin "1") (pinfunction "1_1") (pintype "passive"))
    )
    (net (code "161") (name "Net-(IC22B-VCC)") (class "Default")
      (node (ref "IC22") (pin "20") (pinfunction "VCC_20") (pintype "power_in"))
      (node (ref "SV30") (pin "10") (pinfunction "10_10") (pintype "passive"))
      (node (ref "SV33") (pin "10") (pinfunction "10_10") (pintype "passive"))
      (node (ref "SV34") (pin "10") (pinfunction "10_10") (pintype "passive"))
    )
    (net (code "162") (name "Net-(SV39-Pad1)") (class "Default")
      (node (ref "SV39") (pin "1") (pinfunction "1_1") (pintype "passive"))
      (node (ref "SV45") (pin "1") (pinfunction "1_1") (pintype "passive"))
      (node (ref "U$1") (pin "A3") (pinfunction "A3_A3") (pintype "bidirectional"))
    )
    (net (code "163") (name "Net-(SV39-Pad2)") (class "Default")
      (node (ref "SV39") (pin "2") (pinfunction "2_2") (pintype "passive"))
      (node (ref "SV45") (pin "2") (pinfunction "2_2") (pintype "passive"))
      (node (ref "U$1") (pin "A2") (pinfunction "A2_A2") (pintype "bidirectional"))
    )
    (net (code "164") (name "Net-(SV39-Pad3)") (class "Default")
      (node (ref "SV39") (pin "3") (pinfunction "3_3") (pintype "passive"))
      (node (ref "SV45") (pin "3") (pinfunction "3_3") (pintype "passive"))
      (node (ref "U$1") (pin "A1") (pinfunction "A1_A1") (pintype "bidirectional"))
    )
    (net (code "165") (name "Net-(SV39-Pad4)") (class "Default")
      (node (ref "SV39") (pin "4") (pinfunction "4_4") (pintype "passive"))
      (node (ref "SV45") (pin "4") (pinfunction "4_4") (pintype "passive"))
      (node (ref "U$1") (pin "A0") (pinfunction "A0_A0") (pintype "bidirectional"))
    )
    (net (code "166") (name "Net-(SV39-Pad5)") (class "Default")
      (node (ref "SV39") (pin "5") (pinfunction "5_5") (pintype "passive"))
      (node (ref "SV45") (pin "5") (pinfunction "5_5") (pintype "passive"))
      (node (ref "U$1") (pin "AREF") (pinfunction "AREF_AREF") (pintype "bidirectional"))
    )
    (net (code "167") (name "Net-(SV39-Pad7)") (class "Default")
      (node (ref "SV39") (pin "7") (pinfunction "7_7") (pintype "passive"))
      (node (ref "SV45") (pin "7") (pinfunction "7_7") (pintype "passive"))
      (node (ref "U$1") (pin "D13") (pinfunction "D13_D13") (pintype "bidirectional"))
    )
    (net (code "168") (name "Net-(SV41-Pad1)") (class "Default")
      (node (ref "SV41") (pin "1") (pinfunction "1_1") (pintype "passive"))
      (node (ref "SV44") (pin "1") (pinfunction "1_1") (pintype "passive"))
      (node (ref "U$1") (pin "D6") (pinfunction "D6_D6") (pintype "bidirectional"))
    )
    (net (code "169") (name "Net-(SV41-Pad2)") (class "Default")
      (node (ref "SV41") (pin "2") (pinfunction "2_2") (pintype "passive"))
      (node (ref "SV44") (pin "2") (pinfunction "2_2") (pintype "passive"))
      (node (ref "U$1") (pin "D7") (pinfunction "D7_D7") (pintype "bidirectional"))
    )
    (net (code "170") (name "Net-(SV41-Pad3)") (class "Default")
      (node (ref "SV41") (pin "3") (pinfunction "3_3") (pintype "passive"))
      (node (ref "SV44") (pin "3") (pinfunction "3_3") (pintype "passive"))
      (node (ref "U$1") (pin "D8") (pinfunction "D8_D8") (pintype "bidirectional"))
    )
    (net (code "171") (name "Net-(SV41-Pad4)") (class "Default")
      (node (ref "SV41") (pin "4") (pinfunction "4_4") (pintype "passive"))
      (node (ref "SV44") (pin "4") (pinfunction "4_4") (pintype "passive"))
      (node (ref "U$1") (pin "D9") (pinfunction "D9_D9") (pintype "bidirectional"))
    )
    (net (code "172") (name "Net-(SV41-Pad5)") (class "Default")
      (node (ref "SV41") (pin "5") (pinfunction "5_5") (pintype "passive"))
      (node (ref "SV44") (pin "5") (pinfunction "5_5") (pintype "passive"))
      (node (ref "U$1") (pin "D10") (pinfunction "D10_D10") (pintype "bidirectional"))
    )
    (net (code "173") (name "Net-(SV41-Pad6)") (class "Default")
      (node (ref "SV41") (pin "6") (pinfunction "6_6") (pintype "passive"))
      (node (ref "SV44") (pin "6") (pinfunction "6_6") (pintype "passive"))
      (node (ref "U$1") (pin "D11") (pinfunction "D11_D11") (pintype "bidirectional"))
    )
    (net (code "174") (name "Net-(SV41-Pad7)") (class "Default")
      (node (ref "SV41") (pin "7") (pinfunction "7_7") (pintype "passive"))
      (node (ref "SV44") (pin "7") (pinfunction "7_7") (pintype "passive"))
      (node (ref "U$1") (pin "D12") (pinfunction "D12_D12") (pintype "bidirectional"))
    )
    (net (code "175") (name "Net-(SV47-Pad1)") (class "Default")
      (node (ref "SV47") (pin "1") (pinfunction "1_1") (pintype "passive"))
      (node (ref "SV51") (pin "1") (pinfunction "1_1") (pintype "passive"))
      (node (ref "U$1") (pin "RAW") (pinfunction "RAW_RAW") (pintype "bidirectional"))
    )
    (net (code "176") (name "Net-(SV47-Pad3)") (class "Default")
      (node (ref "SV47") (pin "3") (pinfunction "3_3") (pintype "passive"))
      (node (ref "SV51") (pin "3") (pinfunction "3_3") (pintype "passive"))
      (node (ref "U$1") (pin "RST") (pinfunction "RST_RST") (pintype "bidirectional"))
    )
    (net (code "177") (name "Net-(SV47-Pad5)") (class "Default")
      (node (ref "SV47") (pin "5") (pinfunction "5_5") (pintype "passive"))
      (node (ref "SV51") (pin "5") (pinfunction "5_5") (pintype "passive"))
      (node (ref "U$1") (pin "A7") (pinfunction "A7_A7") (pintype "bidirectional"))
    )
    (net (code "178") (name "Net-(SV47-Pad6)") (class "Default")
      (node (ref "SV47") (pin "6") (pinfunction "6_6") (pintype "passive"))
      (node (ref "SV51") (pin "6") (pinfunction "6_6") (pintype "passive"))
      (node (ref "U$1") (pin "A6") (pinfunction "A6_A6") (pintype "bidirectional"))
    )
    (net (code "179") (name "Net-(SV47-Pad7)") (class "Default")
      (node (ref "SV47") (pin "7") (pinfunction "7_7") (pintype "passive"))
      (node (ref "SV51") (pin "7") (pinfunction "7_7") (pintype "passive"))
      (node (ref "U$1") (pin "A5") (pinfunction "A5_A5") (pintype "bidirectional"))
    )
    (net (code "180") (name "Net-(SV47-Pad8)") (class "Default")
      (node (ref "SV47") (pin "8") (pinfunction "8_8") (pintype "passive"))
      (node (ref "SV51") (pin "8") (pinfunction "8_8") (pintype "passive"))
      (node (ref "U$1") (pin "A4") (pinfunction "A4_A4") (pintype "bidirectional"))
    )
    (net (code "181") (name "Net-(SV52-Pad1)") (class "Default")
      (node (ref "SV52") (pin "1") (pinfunction "1_1") (pintype "passive"))
      (node (ref "SV53") (pin "1") (pinfunction "1_1") (pintype "passive"))
      (node (ref "U$1") (pin "TX0") (pinfunction "TX0_TX0") (pintype "bidirectional"))
    )
    (net (code "182") (name "Net-(SV52-Pad2)") (class "Default")
      (node (ref "SV52") (pin "2") (pinfunction "2_2") (pintype "passive"))
      (node (ref "SV53") (pin "2") (pinfunction "2_2") (pintype "passive"))
      (node (ref "U$1") (pin "RX1") (pinfunction "RX1_RX1") (pintype "bidirectional"))
    )
    (net (code "183") (name "Net-(SV52-Pad3)") (class "Default")
      (node (ref "SV52") (pin "3") (pinfunction "3_3") (pintype "passive"))
      (node (ref "SV53") (pin "3") (pinfunction "3_3") (pintype "passive"))
      (node (ref "U$1") (pin "RST1") (pinfunction "RST1_RST1") (pintype "bidirectional"))
    )
    (net (code "184") (name "Net-(SV52-Pad5)") (class "Default")
      (node (ref "SV52") (pin "5") (pinfunction "5_5") (pintype "passive"))
      (node (ref "SV53") (pin "5") (pinfunction "5_5") (pintype "passive"))
      (node (ref "U$1") (pin "D2") (pinfunction "D2_D2") (pintype "bidirectional"))
    )
    (net (code "185") (name "Net-(SV52-Pad6)") (class "Default")
      (node (ref "SV52") (pin "6") (pinfunction "6_6") (pintype "passive"))
      (node (ref "SV53") (pin "6") (pinfunction "6_6") (pintype "passive"))
      (node (ref "U$1") (pin "D3") (pinfunction "D3_D3") (pintype "bidirectional"))
    )
    (net (code "186") (name "Net-(SV52-Pad7)") (class "Default")
      (node (ref "SV52") (pin "7") (pinfunction "7_7") (pintype "passive"))
      (node (ref "SV53") (pin "7") (pinfunction "7_7") (pintype "passive"))
      (node (ref "U$1") (pin "D4") (pinfunction "D4_D4") (pintype "bidirectional"))
    )
    (net (code "187") (name "Net-(SV52-Pad8)") (class "Default")
      (node (ref "SV52") (pin "8") (pinfunction "8_8") (pintype "passive"))
      (node (ref "SV53") (pin "8") (pinfunction "8_8") (pintype "passive"))
      (node (ref "U$1") (pin "D5") (pinfunction "D5_D5") (pintype "bidirectional"))
    )
    (net (code "188") (name "Net-(U$2-3.3V)") (class "Default")
      (node (ref "SV35") (pin "18") (pinfunction "18_18") (pintype "passive"))
      (node (ref "SV38") (pin "18") (pinfunction "18_18") (pintype "passive"))
      (node (ref "U$2") (pin "P$23") (pinfunction "3.3V_P$23") (pintype "bidirectional"))
    )
    (net (code "189") (name "Net-(U$2-3.3V1)") (class "Default")
      (node (ref "SV36") (pin "1") (pinfunction "1_1") (pintype "passive"))
      (node (ref "SV37") (pin "1") (pinfunction "1_1") (pintype "passive"))
      (node (ref "U$2") (pin "P$20") (pinfunction "3.3V1_P$20") (pintype "bidirectional"))
    )
    (net (code "190") (name "Net-(U$2-PA0)") (class "Default")
      (node (ref "SV35") (pin "5") (pinfunction "5_5") (pintype "passive"))
      (node (ref "SV38") (pin "5") (pinfunction "5_5") (pintype "passive"))
      (node (ref "U$2") (pin "P$36") (pinfunction "PA0_P$36") (pintype "bidirectional"))
    )
    (net (code "191") (name "Net-(U$2-PA1)") (class "Default")
      (node (ref "SV35") (pin "6") (pinfunction "6_6") (pintype "passive"))
      (node (ref "SV38") (pin "6") (pinfunction "6_6") (pintype "passive"))
      (node (ref "U$2") (pin "P$35") (pinfunction "PA1_P$35") (pintype "bidirectional"))
    )
    (net (code "192") (name "Net-(U$2-PA2)") (class "Default")
      (node (ref "SV35") (pin "7") (pinfunction "7_7") (pintype "passive"))
      (node (ref "SV38") (pin "7") (pinfunction "7_7") (pintype "passive"))
      (node (ref "U$2") (pin "P$34") (pinfunction "PA2_P$34") (pintype "bidirectional"))
    )
    (net (code "193") (name "Net-(U$2-PA3)") (class "Default")
      (node (ref "SV35") (pin "8") (pinfunction "8_8") (pintype "passive"))
      (node (ref "SV38") (pin "8") (pinfunction "8_8") (pintype "passive"))
      (node (ref "U$2") (pin "P$33") (pinfunction "PA3_P$33") (pintype "bidirectional"))
    )
    (net (code "194") (name "Net-(U$2-PA4)") (class "Default")
      (node (ref "SV35") (pin "9") (pinfunction "9_9") (pintype "passive"))
      (node (ref "SV38") (pin "9") (pinfunction "9_9") (pintype "passive"))
      (node (ref "U$2") (pin "P$32") (pinfunction "PA4_P$32") (pintype "bidirectional"))
    )
    (net (code "195") (name "Net-(U$2-PA5)") (class "Default")
      (node (ref "SV35") (pin "10") (pinfunction "10_10") (pintype "passive"))
      (node (ref "SV38") (pin "10") (pinfunction "10_10") (pintype "passive"))
      (node (ref "U$2") (pin "P$31") (pinfunction "PA5_P$31") (pintype "bidirectional"))
    )
    (net (code "196") (name "Net-(U$2-PA6)") (class "Default")
      (node (ref "SV35") (pin "11") (pinfunction "11_11") (pintype "passive"))
      (node (ref "SV38") (pin "11") (pinfunction "11_11") (pintype "passive"))
      (node (ref "U$2") (pin "P$30") (pinfunction "PA6_P$30") (pintype "bidirectional"))
    )
    (net (code "197") (name "Net-(U$2-PA7)") (class "Default")
      (node (ref "SV35") (pin "12") (pinfunction "12_12") (pintype "passive"))
      (node (ref "SV38") (pin "12") (pinfunction "12_12") (pintype "passive"))
      (node (ref "U$2") (pin "P$29") (pinfunction "PA7_P$29") (pintype "bidirectional"))
    )
    (net (code "198") (name "Net-(U$2-PA8)") (class "Default")
      (node (ref "SV36") (pin "16") (pinfunction "16_16") (pintype "passive"))
      (node (ref "SV37") (pin "16") (pinfunction "16_16") (pintype "passive"))
      (node (ref "U$2") (pin "P$5") (pinfunction "PA8_P$5") (pintype "bidirectional"))
    )
    (net (code "199") (name "Net-(U$2-PA9)") (class "Default")
      (node (ref "SV36") (pin "15") (pinfunction "15_15") (pintype "passive"))
      (node (ref "SV37") (pin "15") (pinfunction "15_15") (pintype "passive"))
      (node (ref "U$2") (pin "P$6") (pinfunction "PA9_P$6") (pintype "bidirectional"))
    )
    (net (code "200") (name "Net-(U$2-PA10)") (class "Default")
      (node (ref "SV36") (pin "14") (pinfunction "14_14") (pintype "passive"))
      (node (ref "SV37") (pin "14") (pinfunction "14_14") (pintype "passive"))
      (node (ref "U$2") (pin "P$7") (pinfunction "PA10_P$7") (pintype "bidirectional"))
    )
    (net (code "201") (name "Net-(U$2-PA11)") (class "Default")
      (node (ref "SV36") (pin "13") (pinfunction "13_13") (pintype "passive"))
      (node (ref "SV37") (pin "13") (pinfunction "13_13") (pintype "passive"))
      (node (ref "U$2") (pin "P$8") (pinfunction "PA11_P$8") (pintype "bidirectional"))
    )
    (net (code "202") (name "Net-(U$2-PA12)") (class "Default")
      (node (ref "SV36") (pin "12") (pinfunction "12_12") (pintype "passive"))
      (node (ref "SV37") (pin "12") (pinfunction "12_12") (pintype "passive"))
      (node (ref "U$2") (pin "P$9") (pinfunction "PA12_P$9") (pintype "bidirectional"))
    )
    (net (code "203") (name "Net-(U$2-PA15)") (class "Default")
      (node (ref "SV36") (pin "11") (pinfunction "11_11") (pintype "passive"))
      (node (ref "SV37") (pin "11") (pinfunction "11_11") (pintype "passive"))
      (node (ref "U$2") (pin "P$10") (pinfunction "PA15_P$10") (pintype "bidirectional"))
    )
    (net (code "204") (name "Net-(U$2-PB0)") (class "Default")
      (node (ref "SV35") (pin "13") (pinfunction "13_13") (pintype "passive"))
      (node (ref "SV38") (pin "13") (pinfunction "13_13") (pintype "passive"))
      (node (ref "U$2") (pin "P$28") (pinfunction "PB0_P$28") (pintype "bidirectional"))
    )
    (net (code "205") (name "Net-(U$2-PB1)") (class "Default")
      (node (ref "SV35") (pin "14") (pinfunction "14_14") (pintype "passive"))
      (node (ref "SV38") (pin "14") (pinfunction "14_14") (pintype "passive"))
      (node (ref "U$2") (pin "P$27") (pinfunction "PB1_P$27") (pintype "bidirectional"))
    )
    (net (code "206") (name "Net-(U$2-PB3)") (class "Default")
      (node (ref "SV36") (pin "10") (pinfunction "10_10") (pintype "passive"))
      (node (ref "SV37") (pin "10") (pinfunction "10_10") (pintype "passive"))
      (node (ref "U$2") (pin "P$11") (pinfunction "PB3_P$11") (pintype "bidirectional"))
    )
    (net (code "207") (name "Net-(U$2-PB4)") (class "Default")
      (node (ref "SV36") (pin "9") (pinfunction "9_9") (pintype "passive"))
      (node (ref "SV37") (pin "9") (pinfunction "9_9") (pintype "passive"))
      (node (ref "U$2") (pin "P$12") (pinfunction "PB4_P$12") (pintype "bidirectional"))
    )
    (net (code "208") (name "Net-(U$2-PB5)") (class "Default")
      (node (ref "SV36") (pin "8") (pinfunction "8_8") (pintype "passive"))
      (node (ref "SV37") (pin "8") (pinfunction "8_8") (pintype "passive"))
      (node (ref "U$2") (pin "P$13") (pinfunction "PB5_P$13") (pintype "bidirectional"))
    )
    (net (code "209") (name "Net-(U$2-PB6)") (class "Default")
      (node (ref "SV36") (pin "7") (pinfunction "7_7") (pintype "passive"))
      (node (ref "SV37") (pin "7") (pinfunction "7_7") (pintype "passive"))
      (node (ref "U$2") (pin "P$14") (pinfunction "PB6_P$14") (pintype "bidirectional"))
    )
    (net (code "210") (name "Net-(U$2-PB7)") (class "Default")
      (node (ref "SV36") (pin "6") (pinfunction "6_6") (pintype "passive"))
      (node (ref "SV37") (pin "6") (pinfunction "6_6") (pintype "passive"))
      (node (ref "U$2") (pin "P$15") (pinfunction "PB7_P$15") (pintype "bidirectional"))
    )
    (net (code "211") (name "Net-(U$2-PB8)") (class "Default")
      (node (ref "SV36") (pin "5") (pinfunction "5_5") (pintype "passive"))
      (node (ref "SV37") (pin "5") (pinfunction "5_5") (pintype "passive"))
      (node (ref "U$2") (pin "P$16") (pinfunction "PB8_P$16") (pintype "bidirectional"))
    )
    (net (code "212") (name "Net-(U$2-PB9)") (class "Default")
      (node (ref "SV36") (pin "4") (pinfunction "4_4") (pintype "passive"))
      (node (ref "SV37") (pin "4") (pinfunction "4_4") (pintype "passive"))
      (node (ref "U$2") (pin "P$17") (pinfunction "PB9_P$17") (pintype "bidirectional"))
    )
    (net (code "213") (name "Net-(U$2-PB10)") (class "Default")
      (node (ref "SV35") (pin "15") (pinfunction "15_15") (pintype "passive"))
      (node (ref "SV38") (pin "15") (pinfunction "15_15") (pintype "passive"))
      (node (ref "U$2") (pin "P$26") (pinfunction "PB10_P$26") (pintype "bidirectional"))
    )
    (net (code "214") (name "Net-(U$2-PB11)") (class "Default")
      (node (ref "SV35") (pin "16") (pinfunction "16_16") (pintype "passive"))
      (node (ref "SV38") (pin "16") (pinfunction "16_16") (pintype "passive"))
      (node (ref "U$2") (pin "P$25") (pinfunction "PB11_P$25") (pintype "bidirectional"))
    )
    (net (code "215") (name "Net-(U$2-PB12)") (class "Default")
      (node (ref "SV36") (pin "20") (pinfunction "20_20") (pintype "passive"))
      (node (ref "SV37") (pin "20") (pinfunction "20_20") (pintype "passive"))
      (node (ref "U$2") (pin "P$1") (pinfunction "PB12_P$1") (pintype "bidirectional"))
    )
    (net (code "216") (name "Net-(U$2-PB13)") (class "Default")
      (node (ref "SV36") (pin "19") (pinfunction "19_19") (pintype "passive"))
      (node (ref "SV37") (pin "19") (pinfunction "19_19") (pintype "passive"))
      (node (ref "U$2") (pin "P$2") (pinfunction "PB13_P$2") (pintype "bidirectional"))
    )
    (net (code "217") (name "Net-(U$2-PB14)") (class "Default")
      (node (ref "SV36") (pin "18") (pinfunction "18_18") (pintype "passive"))
      (node (ref "SV37") (pin "18") (pinfunction "18_18") (pintype "passive"))
      (node (ref "U$2") (pin "P$3") (pinfunction "PB14_P$3") (pintype "bidirectional"))
    )
    (net (code "218") (name "Net-(U$2-PB15)") (class "Default")
      (node (ref "SV36") (pin "17") (pinfunction "17_17") (pintype "passive"))
      (node (ref "SV37") (pin "17") (pinfunction "17_17") (pintype "passive"))
      (node (ref "U$2") (pin "P$4") (pinfunction "PB15_P$4") (pintype "bidirectional"))
    )
    (net (code "219") (name "Net-(U$2-PC13)") (class "Default")
      (node (ref "SV35") (pin "2") (pinfunction "2_2") (pintype "passive"))
      (node (ref "SV38") (pin "2") (pinfunction "2_2") (pintype "passive"))
      (node (ref "U$2") (pin "P$39") (pinfunction "PC13_P$39") (pintype "bidirectional"))
    )
    (net (code "220") (name "Net-(U$2-PC14)") (class "Default")
      (node (ref "SV35") (pin "3") (pinfunction "3_3") (pintype "passive"))
      (node (ref "SV38") (pin "3") (pinfunction "3_3") (pintype "passive"))
      (node (ref "U$2") (pin "P$38") (pinfunction "PC14_P$38") (pintype "bidirectional"))
    )
    (net (code "221") (name "Net-(U$2-PC15)") (class "Default")
      (node (ref "SV35") (pin "4") (pinfunction "4_4") (pintype "passive"))
      (node (ref "SV38") (pin "4") (pinfunction "4_4") (pintype "passive"))
      (node (ref "U$2") (pin "P$37") (pinfunction "PC15_P$37") (pintype "bidirectional"))
    )
    (net (code "222") (name "Net-(U$2-RESET)") (class "Default")
      (node (ref "SV35") (pin "17") (pinfunction "17_17") (pintype "passive"))
      (node (ref "SV38") (pin "17") (pinfunction "17_17") (pintype "passive"))
      (node (ref "U$2") (pin "P$24") (pinfunction "RESET_P$24") (pintype "bidirectional"))
    )
    (net (code "223") (name "Net-(U$2-VBAT)") (class "Default")
      (node (ref "SV35") (pin "1") (pinfunction "1_1") (pintype "passive"))
      (node (ref "SV38") (pin "1") (pinfunction "1_1") (pintype "passive"))
      (node (ref "U$2") (pin "P$40") (pinfunction "VBAT_P$40") (pintype "bidirectional"))
    )
    (net (code "224") (name "Net-(U$3-EN)") (class "Default")
      (node (ref "SV49") (pin "1") (pinfunction "1_1") (pintype "passive"))
      (node (ref "SV54") (pin "1") (pinfunction "1_1") (pintype "passive"))
      (node (ref "U$3") (pin "16") (pinfunction "EN_16") (pintype "bidirectional"))
    )
    (net (code "225") (name "Net-(U$3-IO1)") (class "Default")
      (node (ref "SV48") (pin "3") (pinfunction "3_3") (pintype "passive"))
      (node (ref "SV50") (pin "3") (pinfunction "3_3") (pintype "passive"))
      (node (ref "U$3") (pin "13") (pinfunction "IO1_13") (pintype "bidirectional"))
    )
    (net (code "226") (name "Net-(U$3-IO2)") (class "Default")
      (node (ref "SV40") (pin "4") (pinfunction "4_4") (pintype "passive"))
      (node (ref "SV46") (pin "4") (pinfunction "4_4") (pintype "passive"))
      (node (ref "U$3") (pin "4") (pinfunction "IO2_4") (pintype "bidirectional"))
    )
    (net (code "227") (name "Net-(U$3-IO3)") (class "Default")
      (node (ref "SV48") (pin "4") (pinfunction "4_4") (pintype "passive"))
      (node (ref "SV50") (pin "4") (pinfunction "4_4") (pintype "passive"))
      (node (ref "U$3") (pin "12") (pinfunction "IO3_12") (pintype "bidirectional"))
    )
    (net (code "228") (name "Net-(U$3-IO4)") (class "Default")
      (node (ref "SV40") (pin "3") (pinfunction "3_3") (pintype "passive"))
      (node (ref "SV46") (pin "3") (pinfunction "3_3") (pintype "passive"))
      (node (ref "U$3") (pin "5") (pinfunction "IO4_5") (pintype "bidirectional"))
    )
    (net (code "229") (name "Net-(U$3-IO5)") (class "Default")
      (node (ref "SV48") (pin "8") (pinfunction "8_8") (pintype "passive"))
      (node (ref "SV50") (pin "8") (pinfunction "8_8") (pintype "passive"))
      (node (ref "U$3") (pin "8") (pinfunction "IO5_8") (pintype "bidirectional"))
    )
    (net (code "230") (name "Net-(U$3-IO12)") (class "Default")
      (node (ref "SV42") (pin "4") (pinfunction "4_4") (pintype "passive"))
      (node (ref "SV43") (pin "4") (pinfunction "4_4") (pintype "passive"))
      (node (ref "U$3") (pin "27") (pinfunction "IO12_27") (pintype "bidirectional"))
    )
    (net (code "231") (name "Net-(U$3-IO13)") (class "Default")
      (node (ref "SV42") (pin "5") (pinfunction "5_5") (pintype "passive"))
      (node (ref "SV43") (pin "5") (pinfunction "5_5") (pintype "passive"))
      (node (ref "U$3") (pin "28") (pinfunction "IO13_28") (pintype "bidirectional"))
    )
    (net (code "232") (name "Net-(U$3-IO14)") (class "Default")
      (node (ref "SV42") (pin "3") (pinfunction "3_3") (pintype "passive"))
      (node (ref "SV43") (pin "3") (pinfunction "3_3") (pintype "passive"))
      (node (ref "U$3") (pin "26") (pinfunction "IO14_26") (pintype "bidirectional"))
    )
    (net (code "233") (name "Net-(U$3-IO15)") (class "Default")
      (node (ref "SV40") (pin "5") (pinfunction "5_5") (pintype "passive"))
      (node (ref "SV46") (pin "5") (pinfunction "5_5") (pintype "passive"))
      (node (ref "U$3") (pin "3") (pinfunction "IO15_3") (pintype "bidirectional"))
    )
    (net (code "234") (name "Net-(U$3-IO16)") (class "Default")
      (node (ref "SV40") (pin "2") (pinfunction "2_2") (pintype "passive"))
      (node (ref "SV46") (pin "2") (pinfunction "2_2") (pintype "passive"))
      (node (ref "U$3") (pin "6") (pinfunction "IO16_6") (pintype "bidirectional"))
    )
    (net (code "235") (name "Net-(U$3-IO17)") (class "Default")
      (node (ref "SV40") (pin "1") (pinfunction "1_1") (pintype "passive"))
      (node (ref "SV46") (pin "1") (pinfunction "1_1") (pintype "passive"))
      (node (ref "U$3") (pin "7") (pinfunction "IO17_7") (pintype "bidirectional"))
    )
    (net (code "236") (name "Net-(U$3-IO18)") (class "Default")
      (node (ref "SV48") (pin "7") (pinfunction "7_7") (pintype "passive"))
      (node (ref "SV50") (pin "7") (pinfunction "7_7") (pintype "passive"))
      (node (ref "U$3") (pin "9") (pinfunction "IO18_9") (pintype "bidirectional"))
    )
    (net (code "237") (name "Net-(U$3-IO19)") (class "Default")
      (node (ref "SV48") (pin "6") (pinfunction "6_6") (pintype "passive"))
      (node (ref "SV50") (pin "6") (pinfunction "6_6") (pintype "passive"))
      (node (ref "U$3") (pin "10") (pinfunction "IO19_10") (pintype "bidirectional"))
    )
    (net (code "238") (name "Net-(U$3-IO21)") (class "Default")
      (node (ref "SV48") (pin "5") (pinfunction "5_5") (pintype "passive"))
      (node (ref "SV50") (pin "5") (pinfunction "5_5") (pintype "passive"))
      (node (ref "U$3") (pin "11") (pinfunction "IO21_11") (pintype "bidirectional"))
    )
    (net (code "239") (name "Net-(U$3-IO22)") (class "Default")
      (node (ref "SV48") (pin "2") (pinfunction "2_2") (pintype "passive"))
      (node (ref "SV50") (pin "2") (pinfunction "2_2") (pintype "passive"))
      (node (ref "U$3") (pin "14") (pinfunction "IO22_14") (pintype "bidirectional"))
    )
    (net (code "240") (name "Net-(U$3-IO23)") (class "Default")
      (node (ref "SV48") (pin "1") (pinfunction "1_1") (pintype "passive"))
      (node (ref "SV50") (pin "1") (pinfunction "1_1") (pintype "passive"))
      (node (ref "U$3") (pin "15") (pinfunction "IO23_15") (pintype "bidirectional"))
    )
    (net (code "241") (name "Net-(U$3-IO25)") (class "Default")
      (node (ref "SV49") (pin "8") (pinfunction "8_8") (pintype "passive"))
      (node (ref "SV54") (pin "8") (pinfunction "8_8") (pintype "passive"))
      (node (ref "U$3") (pin "23") (pinfunction "IO25_23") (pintype "bidirectional"))
    )
    (net (code "242") (name "Net-(U$3-IO26)") (class "Default")
      (node (ref "SV42") (pin "1") (pinfunction "1_1") (pintype "passive"))
      (node (ref "SV43") (pin "1") (pinfunction "1_1") (pintype "passive"))
      (node (ref "U$3") (pin "24") (pinfunction "IO26_24") (pintype "bidirectional"))
    )
    (net (code "243") (name "Net-(U$3-IO27)") (class "Default")
      (node (ref "SV42") (pin "2") (pinfunction "2_2") (pintype "passive"))
      (node (ref "SV43") (pin "2") (pinfunction "2_2") (pintype "passive"))
      (node (ref "U$3") (pin "25") (pinfunction "IO27_25") (pintype "bidirectional"))
    )
    (net (code "244") (name "Net-(U$3-IO32)") (class "Default")
      (node (ref "SV49") (pin "6") (pinfunction "6_6") (pintype "passive"))
      (node (ref "SV54") (pin "6") (pinfunction "6_6") (pintype "passive"))
      (node (ref "U$3") (pin "21") (pinfunction "IO32_21") (pintype "bidirectional"))
    )
    (net (code "245") (name "Net-(U$3-IO33)") (class "Default")
      (node (ref "SV49") (pin "7") (pinfunction "7_7") (pintype "passive"))
      (node (ref "SV54") (pin "7") (pinfunction "7_7") (pintype "passive"))
      (node (ref "U$3") (pin "22") (pinfunction "IO33_22") (pintype "bidirectional"))
    )
    (net (code "246") (name "Net-(U$3-IO34)") (class "Default")
      (node (ref "SV49") (pin "4") (pinfunction "4_4") (pintype "passive"))
      (node (ref "SV54") (pin "4") (pinfunction "4_4") (pintype "passive"))
      (node (ref "U$3") (pin "19") (pinfunction "IO34_19") (pintype "bidirectional"))
    )
    (net (code "247") (name "Net-(U$3-IO35)") (class "Default")
      (node (ref "SV49") (pin "5") (pinfunction "5_5") (pintype "passive"))
      (node (ref "SV54") (pin "5") (pinfunction "5_5") (pintype "passive"))
      (node (ref "U$3") (pin "20") (pinfunction "IO35_20") (pintype "bidirectional"))
    )
    (net (code "248") (name "Net-(U$3-VN)") (class "Default")
      (node (ref "SV49") (pin "3") (pinfunction "3_3") (pintype "passive"))
      (node (ref "SV54") (pin "3") (pinfunction "3_3") (pintype "passive"))
      (node (ref "U$3") (pin "18") (pinfunction "VN_18") (pintype "bidirectional"))
    )
    (net (code "249") (name "Net-(U$3-VP)") (class "Default")
      (node (ref "SV49") (pin "2") (pinfunction "2_2") (pintype "passive"))
      (node (ref "SV54") (pin "2") (pinfunction "2_2") (pintype "passive"))
      (node (ref "U$3") (pin "17") (pinfunction "VP_17") (pintype "bidirectional"))
    )
    (net (code "250") (name "VCC") (class "Default")
      (node (ref "C1") (pin "1") (pinfunction "1_1") (pintype "passive"))
      (node (ref "C2") (pin "1") (pinfunction "1_1") (pintype "passive"))
      (node (ref "C3") (pin "1") (pinfunction "1_1") (pintype "passive"))
      (node (ref "C4") (pin "1") (pinfunction "1_1") (pintype "passive"))
      (node (ref "C5") (pin "1") (pinfunction "1_1") (pintype "passive"))
      (node (ref "C6") (pin "1") (pinfunction "1_1") (pintype "passive"))
      (node (ref "C7") (pin "1") (pinfunction "1_1") (pintype "passive"))
      (node (ref "C8") (pin "1") (pinfunction "1_1") (pintype "passive"))
      (node (ref "C9") (pin "1") (pinfunction "1_1") (pintype "passive"))
      (node (ref "SV27") (pin "1") (pinfunction "1_1") (pintype "passive"))
      (node (ref "SV27") (pin "10") (pinfunction "10_10") (pintype "passive"))
      (node (ref "SV27") (pin "11") (pinfunction "11_11") (pintype "passive"))
      (node (ref "SV27") (pin "12") (pinfunction "12_12") (pintype "passive"))
      (node (ref "SV27") (pin "13") (pinfunction "13_13") (pintype "passive"))
      (node (ref "SV27") (pin "14") (pinfunction "14_14") (pintype "passive"))
      (node (ref "SV27") (pin "15") (pinfunction "15_15") (pintype "passive"))
      (node (ref "SV27") (pin "16") (pinfunction "16_16") (pintype "passive"))
      (node (ref "SV27") (pin "17") (pinfunction "17_17") (pintype "passive"))
      (node (ref "SV27") (pin "18") (pinfunction "18_18") (pintype "passive"))
      (node (ref "SV27") (pin "19") (pinfunction "19_19") (pintype "passive"))
      (node (ref "SV27") (pin "2") (pinfunction "2_2") (pintype "passive"))
      (node (ref "SV27") (pin "20") (pinfunction "20_20") (pintype "passive"))
      (node (ref "SV27") (pin "3") (pinfunction "3_3") (pintype "passive"))
      (node (ref "SV27") (pin "4") (pinfunction "4_4") (pintype "passive"))
      (node (ref "SV27") (pin "5") (pinfunction "5_5") (pintype "passive"))
      (node (ref "SV27") (pin "6") (pinfunction "6_6") (pintype "passive"))
      (node (ref "SV27") (pin "7") (pinfunction "7_7") (pintype "passive"))
      (node (ref "SV27") (pin "8") (pinfunction "8_8") (pintype "passive"))
      (node (ref "SV27") (pin "9") (pinfunction "9_9") (pintype "passive"))
      (node (ref "SV28") (pin "1") (pinfunction "1_1") (pintype "passive"))
      (node (ref "SV28") (pin "10") (pinfunction "10_10") (pintype "passive"))
      (node (ref "SV28") (pin "11") (pinfunction "11_11") (pintype "passive"))
      (node (ref "SV28") (pin "12") (pinfunction "12_12") (pintype "passive"))
      (node (ref "SV28") (pin "13") (pinfunction "13_13") (pintype "passive"))
      (node (ref "SV28") (pin "14") (pinfunction "14_14") (pintype "passive"))
      (node (ref "SV28") (pin "15") (pinfunction "15_15") (pintype "passive"))
      (node (ref "SV28") (pin "16") (pinfunction "16_16") (pintype "passive"))
      (node (ref "SV28") (pin "17") (pinfunction "17_17") (pintype "passive"))
      (node (ref "SV28") (pin "18") (pinfunction "18_18") (pintype "passive"))
      (node (ref "SV28") (pin "19") (pinfunction "19_19") (pintype "passive"))
      (node (ref "SV28") (pin "2") (pinfunction "2_2") (pintype "passive"))
      (node (ref "SV28") (pin "20") (pinfunction "20_20") (pintype "passive"))
      (node (ref "SV28") (pin "3") (pinfunction "3_3") (pintype "passive"))
      (node (ref "SV28") (pin "4") (pinfunction "4_4") (pintype "passive"))
      (node (ref "SV28") (pin "5") (pinfunction "5_5") (pintype "passive"))
      (node (ref "SV28") (pin "6") (pinfunction "6_6") (pintype "passive"))
      (node (ref "SV28") (pin "7") (pinfunction "7_7") (pintype "passive"))
      (node (ref "SV28") (pin "8") (pinfunction "8_8") (pintype "passive"))
      (node (ref "SV28") (pin "9") (pinfunction "9_9") (pintype "passive"))
      (node (ref "SV39") (pin "6") (pinfunction "6_6") (pintype "passive"))
      (node (ref "SV40") (pin "7") (pinfunction "7_7") (pintype "passive"))
      (node (ref "SV45") (pin "6") (pinfunction "6_6") (pintype "passive"))
      (node (ref "SV46") (pin "7") (pinfunction "7_7") (pintype "passive"))
      (node (ref "SV5") (pin "1") (pinfunction "1_1") (pintype "passive"))
      (node (ref "SV5") (pin "10") (pinfunction "10_10") (pintype "passive"))
      (node (ref "SV5") (pin "11") (pinfunction "11_11") (pintype "passive"))
      (node (ref "SV5") (pin "12") (pinfunction "12_12") (pintype "passive"))
      (node (ref "SV5") (pin "13") (pinfunction "13_13") (pintype "passive"))
      (node (ref "SV5") (pin "14") (pinfunction "14_14") (pintype "passive"))
      (node (ref "SV5") (pin "15") (pinfunction "15_15") (pintype "passive"))
      (node (ref "SV5") (pin "16") (pinfunction "16_16") (pintype "passive"))
      (node (ref "SV5") (pin "17") (pinfunction "17_17") (pintype "passive"))
      (node (ref "SV5") (pin "18") (pinfunction "18_18") (pintype "passive"))
      (node (ref "SV5") (pin "19") (pinfunction "19_19") (pintype "passive"))
      (node (ref "SV5") (pin "2") (pinfunction "2_2") (pintype "passive"))
      (node (ref "SV5") (pin "20") (pinfunction "20_20") (pintype "passive"))
      (node (ref "SV5") (pin "3") (pinfunction "3_3") (pintype "passive"))
      (node (ref "SV5") (pin "4") (pinfunction "4_4") (pintype "passive"))
      (node (ref "SV5") (pin "5") (pinfunction "5_5") (pintype "passive"))
      (node (ref "SV5") (pin "6") (pinfunction "6_6") (pintype "passive"))
      (node (ref "SV5") (pin "7") (pinfunction "7_7") (pintype "passive"))
      (node (ref "SV5") (pin "8") (pinfunction "8_8") (pintype "passive"))
      (node (ref "SV5") (pin "9") (pinfunction "9_9") (pintype "passive"))
      (node (ref "SV6") (pin "1") (pinfunction "1_1") (pintype "passive"))
      (node (ref "SV6") (pin "10") (pinfunction "10_10") (pintype "passive"))
      (node (ref "SV6") (pin "11") (pinfunction "11_11") (pintype "passive"))
      (node (ref "SV6") (pin "12") (pinfunction "12_12") (pintype "passive"))
      (node (ref "SV6") (pin "13") (pinfunction "13_13") (pintype "passive"))
      (node (ref "SV6") (pin "14") (pinfunction "14_14") (pintype "passive"))
      (node (ref "SV6") (pin "15") (pinfunction "15_15") (pintype "passive"))
      (node (ref "SV6") (pin "16") (pinfunction "16_16") (pintype "passive"))
      (node (ref "SV6") (pin "17") (pinfunction "17_17") (pintype "passive"))
      (node (ref "SV6") (pin "18") (pinfunction "18_18") (pintype "passive"))
      (node (ref "SV6") (pin "19") (pinfunction "19_19") (pintype "passive"))
      (node (ref "SV6") (pin "2") (pinfunction "2_2") (pintype "passive"))
      (node (ref "SV6") (pin "20") (pinfunction "20_20") (pintype "passive"))
      (node (ref "SV6") (pin "3") (pinfunction "3_3") (pintype "passive"))
      (node (ref "SV6") (pin "4") (pinfunction "4_4") (pintype "passive"))
      (node (ref "SV6") (pin "5") (pinfunction "5_5") (pintype "passive"))
      (node (ref "SV6") (pin "6") (pinfunction "6_6") (pintype "passive"))
      (node (ref "SV6") (pin "7") (pinfunction "7_7") (pintype "passive"))
      (node (ref "SV6") (pin "8") (pinfunction "8_8") (pintype "passive"))
      (node (ref "SV6") (pin "9") (pinfunction "9_9") (pintype "passive"))
      (node (ref "SV7") (pin "1") (pinfunction "1_1") (pintype "passive"))
      (node (ref "SV7") (pin "10") (pinfunction "10_10") (pintype "passive"))
      (node (ref "SV7") (pin "11") (pinfunction "11_11") (pintype "passive"))
      (node (ref "SV7") (pin "12") (pinfunction "12_12") (pintype "passive"))
      (node (ref "SV7") (pin "13") (pinfunction "13_13") (pintype "passive"))
      (node (ref "SV7") (pin "14") (pinfunction "14_14") (pintype "passive"))
      (node (ref "SV7") (pin "15") (pinfunction "15_15") (pintype "passive"))
      (node (ref "SV7") (pin "16") (pinfunction "16_16") (pintype "passive"))
      (node (ref "SV7") (pin "17") (pinfunction "17_17") (pintype "passive"))
      (node (ref "SV7") (pin "18") (pinfunction "18_18") (pintype "passive"))
      (node (ref "SV7") (pin "19") (pinfunction "19_19") (pintype "passive"))
      (node (ref "SV7") (pin "2") (pinfunction "2_2") (pintype "passive"))
      (node (ref "SV7") (pin "20") (pinfunction "20_20") (pintype "passive"))
      (node (ref "SV7") (pin "3") (pinfunction "3_3") (pintype "passive"))
      (node (ref "SV7") (pin "4") (pinfunction "4_4") (pintype "passive"))
      (node (ref "SV7") (pin "5") (pinfunction "5_5") (pintype "passive"))
      (node (ref "SV7") (pin "6") (pinfunction "6_6") (pintype "passive"))
      (node (ref "SV7") (pin "7") (pinfunction "7_7") (pintype "passive"))
      (node (ref "SV7") (pin "8") (pinfunction "8_8") (pintype "passive"))
      (node (ref "SV7") (pin "9") (pinfunction "9_9") (pintype "passive"))
      (node (ref "SV8") (pin "1") (pinfunction "1_1") (pintype "passive"))
      (node (ref "SV8") (pin "10") (pinfunction "10_10") (pintype "passive"))
      (node (ref "SV8") (pin "11") (pinfunction "11_11") (pintype "passive"))
      (node (ref "SV8") (pin "12") (pinfunction "12_12") (pintype "passive"))
      (node (ref "SV8") (pin "13") (pinfunction "13_13") (pintype "passive"))
      (node (ref "SV8") (pin "14") (pinfunction "14_14") (pintype "passive"))
      (node (ref "SV8") (pin "15") (pinfunction "15_15") (pintype "passive"))
      (node (ref "SV8") (pin "16") (pinfunction "16_16") (pintype "passive"))
      (node (ref "SV8") (pin "17") (pinfunction "17_17") (pintype "passive"))
      (node (ref "SV8") (pin "18") (pinfunction "18_18") (pintype "passive"))
      (node (ref "SV8") (pin "19") (pinfunction "19_19") (pintype "passive"))
      (node (ref "SV8") (pin "2") (pinfunction "2_2") (pintype "passive"))
      (node (ref "SV8") (pin "20") (pinfunction "20_20") (pintype "passive"))
      (node (ref "SV8") (pin "3") (pinfunction "3_3") (pintype "passive"))
      (node (ref "SV8") (pin "4") (pinfunction "4_4") (pintype "passive"))
      (node (ref "SV8") (pin "5") (pinfunction "5_5") (pintype "passive"))
      (node (ref "SV8") (pin "6") (pinfunction "6_6") (pintype "passive"))
      (node (ref "SV8") (pin "7") (pinfunction "7_7") (pintype "passive"))
      (node (ref "SV8") (pin "8") (pinfunction "8_8") (pintype "passive"))
      (node (ref "SV8") (pin "9") (pinfunction "9_9") (pintype "passive"))
      (node (ref "U$1") (pin "3.3V") (pinfunction "3.3V_3.3V") (pintype "bidirectional"))
      (node (ref "U$3") (pin "1") (pinfunction "3V3_1") (pintype "bidirectional"))
    )
    (net (code "251") (name "VS") (class "Default")
      (node (ref "SV36") (pin "3") (pinfunction "3_3") (pintype "passive"))
      (node (ref "SV37") (pin "3") (pinfunction "3_3") (pintype "passive"))
      (node (ref "SV42") (pin "7") (pinfunction "7_7") (pintype "passive"))
      (node (ref "SV43") (pin "7") (pinfunction "7_7") (pintype "passive"))
      (node (ref "SV47") (pin "4") (pinfunction "4_4") (pintype "passive"))
      (node (ref "SV51") (pin "4") (pinfunction "4_4") (pintype "passive"))
      (node (ref "U$1") (pin "5V") (pinfunction "5.5V_5V") (pintype "bidirectional"))
      (node (ref "U$2") (pin "P$18") (pinfunction "5V_P$18") (pintype "bidirectional"))
      (node (ref "U$3") (pin "30") (pinfunction "VIN_30") (pintype "bidirectional"))
    )
    (net (code "252") (name "unconnected-(IC8A-1A-Pad2)") (class "Default")
      (node (ref "IC8") (pin "2") (pinfunction "1A_2") (pintype "input"))
    )
    (net (code "253") (name "unconnected-(IC8A-1B-Pad3)") (class "Default")
      (node (ref "IC8") (pin "3") (pinfunction "1B_3") (pintype "input"))
    )
    (net (code "254") (name "unconnected-(IC8A-1Y-Pad4)") (class "Default")
      (node (ref "IC8") (pin "4") (pinfunction "1Y_4") (pintype "output"))
    )
    (net (code "255") (name "unconnected-(IC8A-2A-Pad5)") (class "Default")
      (node (ref "IC8") (pin "5") (pinfunction "2A_5") (pintype "input"))
    )
    (net (code "256") (name "unconnected-(IC8A-2B-Pad6)") (class "Default")
      (node (ref "IC8") (pin "6") (pinfunction "2B_6") (pintype "input"))
    )
    (net (code "257") (name "unconnected-(IC8A-2Y-Pad7)") (class "Default")
      (node (ref "IC8") (pin "7") (pinfunction "2Y_7") (pintype "output"))
    )
    (net (code "258") (name "unconnected-(IC8A-3A-Pad11)") (class "Default")
      (node (ref "IC8") (pin "11") (pinfunction "3A_11") (pintype "input"))
    )
    (net (code "259") (name "unconnected-(IC8A-3B-Pad10)") (class "Default")
      (node (ref "IC8") (pin "10") (pinfunction "3B_10") (pintype "input"))
    )
    (net (code "260") (name "unconnected-(IC8A-3Y-Pad9)") (class "Default")
      (node (ref "IC8") (pin "9") (pinfunction "3Y_9") (pintype "output"))
    )
    (net (code "261") (name "unconnected-(IC8A-4A-Pad14)") (class "Default")
      (node (ref "IC8") (pin "14") (pinfunction "4A_14") (pintype "input"))
    )
    (net (code "262") (name "unconnected-(IC8A-4B-Pad13)") (class "Default")
      (node (ref "IC8") (pin "13") (pinfunction "4B_13") (pintype "input"))
    )
    (net (code "263") (name "unconnected-(IC8A-4Y-Pad12)") (class "Default")
      (node (ref "IC8") (pin "12") (pinfunction "4Y_12") (pintype "output"))
    )
    (net (code "264") (name "unconnected-(IC8A-G-Pad15)") (class "Default")
      (node (ref "IC8") (pin "15") (pinfunction "G_15") (pintype "input"))
    )
    (net (code "265") (name "unconnected-(IC8A-~{A}{slash}B-Pad1)") (class "Default")
      (node (ref "IC8") (pin "1") (pinfunction "~{A}/B_1") (pintype "input"))
    )
    (net (code "266") (name "unconnected-(IC9A-1A-Pad2)") (class "Default")
      (node (ref "IC9") (pin "2") (pinfunction "1A_2") (pintype "input"))
    )
    (net (code "267") (name "unconnected-(IC9A-1B-Pad3)") (class "Default")
      (node (ref "IC9") (pin "3") (pinfunction "1B_3") (pintype "input"))
    )
    (net (code "268") (name "unconnected-(IC9A-1Y-Pad4)") (class "Default")
      (node (ref "IC9") (pin "4") (pinfunction "1Y_4") (pintype "output"))
    )
    (net (code "269") (name "unconnected-(IC9A-2A-Pad5)") (class "Default")
      (node (ref "IC9") (pin "5") (pinfunction "2A_5") (pintype "input"))
    )
    (net (code "270") (name "unconnected-(IC9A-2B-Pad6)") (class "Default")
      (node (ref "IC9") (pin "6") (pinfunction "2B_6") (pintype "input"))
    )
    (net (code "271") (name "unconnected-(IC9A-2Y-Pad7)") (class "Default")
      (node (ref "IC9") (pin "7") (pinfunction "2Y_7") (pintype "output"))
    )
    (net (code "272") (name "unconnected-(IC9A-3A-Pad11)") (class "Default")
      (node (ref "IC9") (pin "11") (pinfunction "3A_11") (pintype "input"))
    )
    (net (code "273") (name "unconnected-(IC9A-3B-Pad10)") (class "Default")
      (node (ref "IC9") (pin "10") (pinfunction "3B_10") (pintype "input"))
    )
    (net (code "274") (name "unconnected-(IC9A-3Y-Pad9)") (class "Default")
      (node (ref "IC9") (pin "9") (pinfunction "3Y_9") (pintype "output"))
    )
    (net (code "275") (name "unconnected-(IC9A-4A-Pad14)") (class "Default")
      (node (ref "IC9") (pin "14") (pinfunction "4A_14") (pintype "input"))
    )
    (net (code "276") (name "unconnected-(IC9A-4B-Pad13)") (class "Default")
      (node (ref "IC9") (pin "13") (pinfunction "4B_13") (pintype "input"))
    )
    (net (code "277") (name "unconnected-(IC9A-4Y-Pad12)") (class "Default")
      (node (ref "IC9") (pin "12") (pinfunction "4Y_12") (pintype "output"))
    )
    (net (code "278") (name "unconnected-(IC9A-G-Pad15)") (class "Default")
      (node (ref "IC9") (pin "15") (pinfunction "G_15") (pintype "input"))
    )
    (net (code "279") (name "unconnected-(IC9A-~{A}{slash}B-Pad1)") (class "Default")
      (node (ref "IC9") (pin "1") (pinfunction "~{A}/B_1") (pintype "input"))
    )
    (net (code "280") (name "unconnected-(IC12A-1A-Pad2)") (class "Default")
      (node (ref "IC12") (pin "2") (pinfunction "1A_2") (pintype "input"))
    )
    (net (code "281") (name "unconnected-(IC12A-1B-Pad3)") (class "Default")
      (node (ref "IC12") (pin "3") (pinfunction "1B_3") (pintype "input"))
    )
    (net (code "282") (name "unconnected-(IC12A-1Y-Pad4)") (class "Default")
      (node (ref "IC12") (pin "4") (pinfunction "1Y_4") (pintype "output"))
    )
    (net (code "283") (name "unconnected-(IC12A-2A-Pad5)") (class "Default")
      (node (ref "IC12") (pin "5") (pinfunction "2A_5") (pintype "input"))
    )
    (net (code "284") (name "unconnected-(IC12A-2B-Pad6)") (class "Default")
      (node (ref "IC12") (pin "6") (pinfunction "2B_6") (pintype "input"))
    )
    (net (code "285") (name "unconnected-(IC12A-2Y-Pad7)") (class "Default")
      (node (ref "IC12") (pin "7") (pinfunction "2Y_7") (pintype "output"))
    )
    (net (code "286") (name "unconnected-(IC12A-3A-Pad11)") (class "Default")
      (node (ref "IC12") (pin "11") (pinfunction "3A_11") (pintype "input"))
    )
    (net (code "287") (name "unconnected-(IC12A-3B-Pad10)") (class "Default")
      (node (ref "IC12") (pin "10") (pinfunction "3B_10") (pintype "input"))
    )
    (net (code "288") (name "unconnected-(IC12A-3Y-Pad9)") (class "Default")
      (node (ref "IC12") (pin "9") (pinfunction "3Y_9") (pintype "output"))
    )
    (net (code "289") (name "unconnected-(IC12A-4A-Pad14)") (class "Default")
      (node (ref "IC12") (pin "14") (pinfunction "4A_14") (pintype "input"))
    )
    (net (code "290") (name "unconnected-(IC12A-4B-Pad13)") (class "Default")
      (node (ref "IC12") (pin "13") (pinfunction "4B_13") (pintype "input"))
    )
    (net (code "291") (name "unconnected-(IC12A-4Y-Pad12)") (class "Default")
      (node (ref "IC12") (pin "12") (pinfunction "4Y_12") (pintype "output"))
    )
    (net (code "292") (name "unconnected-(IC12A-G-Pad15)") (class "Default")
      (node (ref "IC12") (pin "15") (pinfunction "G_15") (pintype "input"))
    )
    (net (code "293") (name "unconnected-(IC12A-~{A}{slash}B-Pad1)") (class "Default")
      (node (ref "IC12") (pin "1") (pinfunction "~{A}/B_1") (pintype "input"))
    )
    (net (code "294") (name "unconnected-(IC13A-1A-Pad2)") (class "Default")
      (node (ref "IC13") (pin "2") (pinfunction "1A_2") (pintype "input"))
    )
    (net (code "295") (name "unconnected-(IC13A-1B-Pad3)") (class "Default")
      (node (ref "IC13") (pin "3") (pinfunction "1B_3") (pintype "input"))
    )
    (net (code "296") (name "unconnected-(IC13A-1Y-Pad4)") (class "Default")
      (node (ref "IC13") (pin "4") (pinfunction "1Y_4") (pintype "output"))
    )
    (net (code "297") (name "unconnected-(IC13A-2A-Pad5)") (class "Default")
      (node (ref "IC13") (pin "5") (pinfunction "2A_5") (pintype "input"))
    )
    (net (code "298") (name "unconnected-(IC13A-2B-Pad6)") (class "Default")
      (node (ref "IC13") (pin "6") (pinfunction "2B_6") (pintype "input"))
    )
    (net (code "299") (name "unconnected-(IC13A-2Y-Pad7)") (class "Default")
      (node (ref "IC13") (pin "7") (pinfunction "2Y_7") (pintype "output"))
    )
    (net (code "300") (name "unconnected-(IC13A-3A-Pad11)") (class "Default")
      (node (ref "IC13") (pin "11") (pinfunction "3A_11") (pintype "input"))
    )
    (net (code "301") (name "unconnected-(IC13A-3B-Pad10)") (class "Default")
      (node (ref "IC13") (pin "10") (pinfunction "3B_10") (pintype "input"))
    )
    (net (code "302") (name "unconnected-(IC13A-3Y-Pad9)") (class "Default")
      (node (ref "IC13") (pin "9") (pinfunction "3Y_9") (pintype "output"))
    )
    (net (code "303") (name "unconnected-(IC13A-4A-Pad14)") (class "Default")
      (node (ref "IC13") (pin "14") (pinfunction "4A_14") (pintype "input"))
    )
    (net (code "304") (name "unconnected-(IC13A-4B-Pad13)") (class "Default")
      (node (ref "IC13") (pin "13") (pinfunction "4B_13") (pintype "input"))
    )
    (net (code "305") (name "unconnected-(IC13A-4Y-Pad12)") (class "Default")
      (node (ref "IC13") (pin "12") (pinfunction "4Y_12") (pintype "output"))
    )
    (net (code "306") (name "unconnected-(IC13A-G-Pad15)") (class "Default")
      (node (ref "IC13") (pin "15") (pinfunction "G_15") (pintype "input"))
    )
    (net (code "307") (name "unconnected-(IC13A-~{A}{slash}B-Pad1)") (class "Default")
      (node (ref "IC13") (pin "1") (pinfunction "~{A}/B_1") (pintype "input"))
    )
    (net (code "308") (name "unconnected-(IC15A-1A-Pad2)") (class "Default")
      (node (ref "IC15") (pin "2") (pinfunction "1A_2") (pintype "input"))
    )
    (net (code "309") (name "unconnected-(IC15A-1B-Pad3)") (class "Default")
      (node (ref "IC15") (pin "3") (pinfunction "1B_3") (pintype "input"))
    )
    (net (code "310") (name "unconnected-(IC15A-1Y-Pad4)") (class "Default")
      (node (ref "IC15") (pin "4") (pinfunction "1Y_4") (pintype "output"))
    )
    (net (code "311") (name "unconnected-(IC15A-2A-Pad5)") (class "Default")
      (node (ref "IC15") (pin "5") (pinfunction "2A_5") (pintype "input"))
    )
    (net (code "312") (name "unconnected-(IC15A-2B-Pad6)") (class "Default")
      (node (ref "IC15") (pin "6") (pinfunction "2B_6") (pintype "input"))
    )
    (net (code "313") (name "unconnected-(IC15A-2Y-Pad7)") (class "Default")
      (node (ref "IC15") (pin "7") (pinfunction "2Y_7") (pintype "output"))
    )
    (net (code "314") (name "unconnected-(IC15A-3A-Pad11)") (class "Default")
      (node (ref "IC15") (pin "11") (pinfunction "3A_11") (pintype "input"))
    )
    (net (code "315") (name "unconnected-(IC15A-3B-Pad10)") (class "Default")
      (node (ref "IC15") (pin "10") (pinfunction "3B_10") (pintype "input"))
    )
    (net (code "316") (name "unconnected-(IC15A-3Y-Pad9)") (class "Default")
      (node (ref "IC15") (pin "9") (pinfunction "3Y_9") (pintype "output"))
    )
    (net (code "317") (name "unconnected-(IC15A-4A-Pad14)") (class "Default")
      (node (ref "IC15") (pin "14") (pinfunction "4A_14") (pintype "input"))
    )
    (net (code "318") (name "unconnected-(IC15A-4B-Pad13)") (class "Default")
      (node (ref "IC15") (pin "13") (pinfunction "4B_13") (pintype "input"))
    )
    (net (code "319") (name "unconnected-(IC15A-4Y-Pad12)") (class "Default")
      (node (ref "IC15") (pin "12") (pinfunction "4Y_12") (pintype "output"))
    )
    (net (code "320") (name "unconnected-(IC15A-G-Pad15)") (class "Default")
      (node (ref "IC15") (pin "15") (pinfunction "G_15") (pintype "input"))
    )
    (net (code "321") (name "unconnected-(IC15A-~{A}{slash}B-Pad1)") (class "Default")
      (node (ref "IC15") (pin "1") (pinfunction "~{A}/B_1") (pintype "input"))
    )
    (net (code "322") (name "unconnected-(IC16A-1A-Pad2)") (class "Default")
      (node (ref "IC16") (pin "2") (pinfunction "1A_2") (pintype "input"))
    )
    (net (code "323") (name "unconnected-(IC16A-1B-Pad3)") (class "Default")
      (node (ref "IC16") (pin "3") (pinfunction "1B_3") (pintype "input"))
    )
    (net (code "324") (name "unconnected-(IC16A-1Y-Pad4)") (class "Default")
      (node (ref "IC16") (pin "4") (pinfunction "1Y_4") (pintype "output"))
    )
    (net (code "325") (name "unconnected-(IC16A-2A-Pad5)") (class "Default")
      (node (ref "IC16") (pin "5") (pinfunction "2A_5") (pintype "input"))
    )
    (net (code "326") (name "unconnected-(IC16A-2B-Pad6)") (class "Default")
      (node (ref "IC16") (pin "6") (pinfunction "2B_6") (pintype "input"))
    )
    (net (code "327") (name "unconnected-(IC16A-2Y-Pad7)") (class "Default")
      (node (ref "IC16") (pin "7") (pinfunction "2Y_7") (pintype "output"))
    )
    (net (code "328") (name "unconnected-(IC16A-3A-Pad11)") (class "Default")
      (node (ref "IC16") (pin "11") (pinfunction "3A_11") (pintype "input"))
    )
    (net (code "329") (name "unconnected-(IC16A-3B-Pad10)") (class "Default")
      (node (ref "IC16") (pin "10") (pinfunction "3B_10") (pintype "input"))
    )
    (net (code "330") (name "unconnected-(IC16A-3Y-Pad9)") (class "Default")
      (node (ref "IC16") (pin "9") (pinfunction "3Y_9") (pintype "output"))
    )
    (net (code "331") (name "unconnected-(IC16A-4A-Pad14)") (class "Default")
      (node (ref "IC16") (pin "14") (pinfunction "4A_14") (pintype "input"))
    )
    (net (code "332") (name "unconnected-(IC16A-4B-Pad13)") (class "Default")
      (node (ref "IC16") (pin "13") (pinfunction "4B_13") (pintype "input"))
    )
    (net (code "333") (name "unconnected-(IC16A-4Y-Pad12)") (class "Default")
      (node (ref "IC16") (pin "12") (pinfunction "4Y_12") (pintype "output"))
    )
    (net (code "334") (name "unconnected-(IC16A-G-Pad15)") (class "Default")
      (node (ref "IC16") (pin "15") (pinfunction "G_15") (pintype "input"))
    )
    (net (code "335") (name "unconnected-(IC16A-~{A}{slash}B-Pad1)") (class "Default")
      (node (ref "IC16") (pin "1") (pinfunction "~{A}/B_1") (pintype "input"))
    )
    (net (code "336") (name "unconnected-(IC23A-1A-Pad2)") (class "Default")
      (node (ref "IC23") (pin "2") (pinfunction "1A_2") (pintype "input"))
    )
    (net (code "337") (name "unconnected-(IC23A-1B-Pad3)") (class "Default")
      (node (ref "IC23") (pin "3") (pinfunction "1B_3") (pintype "input"))
    )
    (net (code "338") (name "unconnected-(IC23A-1Y-Pad4)") (class "Default")
      (node (ref "IC23") (pin "4") (pinfunction "1Y_4") (pintype "output"))
    )
    (net (code "339") (name "unconnected-(IC23A-2A-Pad5)") (class "Default")
      (node (ref "IC23") (pin "5") (pinfunction "2A_5") (pintype "input"))
    )
    (net (code "340") (name "unconnected-(IC23A-2B-Pad6)") (class "Default")
      (node (ref "IC23") (pin "6") (pinfunction "2B_6") (pintype "input"))
    )
    (net (code "341") (name "unconnected-(IC23A-2Y-Pad7)") (class "Default")
      (node (ref "IC23") (pin "7") (pinfunction "2Y_7") (pintype "output"))
    )
    (net (code "342") (name "unconnected-(IC23A-3A-Pad11)") (class "Default")
      (node (ref "IC23") (pin "11") (pinfunction "3A_11") (pintype "input"))
    )
    (net (code "343") (name "unconnected-(IC23A-3B-Pad10)") (class "Default")
      (node (ref "IC23") (pin "10") (pinfunction "3B_10") (pintype "input"))
    )
    (net (code "344") (name "unconnected-(IC23A-3Y-Pad9)") (class "Default")
      (node (ref "IC23") (pin "9") (pinfunction "3Y_9") (pintype "output"))
    )
    (net (code "345") (name "unconnected-(IC23A-4A-Pad14)") (class "Default")
      (node (ref "IC23") (pin "14") (pinfunction "4A_14") (pintype "input"))
    )
    (net (code "346") (name "unconnected-(IC23A-4B-Pad13)") (class "Default")
      (node (ref "IC23") (pin "13") (pinfunction "4B_13") (pintype "input"))
    )
    (net (code "347") (name "unconnected-(IC23A-4Y-Pad12)") (class "Default")
      (node (ref "IC23") (pin "12") (pinfunction "4Y_12") (pintype "output"))
    )
    (net (code "348") (name "unconnected-(IC23A-G-Pad15)") (class "Default")
      (node (ref "IC23") (pin "15") (pinfunction "G_15") (pintype "input"))
    )
    (net (code "349") (name "unconnected-(IC23A-~{A}{slash}B-Pad1)") (class "Default")
      (node (ref "IC23") (pin "1") (pinfunction "~{A}/B_1") (pintype "input"))
    )
    (net (code "350") (name "unconnected-(IC24A-1A-Pad2)") (class "Default")
      (node (ref "IC24") (pin "2") (pinfunction "1A_2") (pintype "input"))
    )
    (net (code "351") (name "unconnected-(IC24A-1B-Pad3)") (class "Default")
      (node (ref "IC24") (pin "3") (pinfunction "1B_3") (pintype "input"))
    )
    (net (code "352") (name "unconnected-(IC24A-1Y-Pad4)") (class "Default")
      (node (ref "IC24") (pin "4") (pinfunction "1Y_4") (pintype "output"))
    )
    (net (code "353") (name "unconnected-(IC24A-2A-Pad5)") (class "Default")
      (node (ref "IC24") (pin "5") (pinfunction "2A_5") (pintype "input"))
    )
    (net (code "354") (name "unconnected-(IC24A-2B-Pad6)") (class "Default")
      (node (ref "IC24") (pin "6") (pinfunction "2B_6") (pintype "input"))
    )
    (net (code "355") (name "unconnected-(IC24A-2Y-Pad7)") (class "Default")
      (node (ref "IC24") (pin "7") (pinfunction "2Y_7") (pintype "output"))
    )
    (net (code "356") (name "unconnected-(IC24A-3A-Pad11)") (class "Default")
      (node (ref "IC24") (pin "11") (pinfunction "3A_11") (pintype "input"))
    )
    (net (code "357") (name "unconnected-(IC24A-3B-Pad10)") (class "Default")
      (node (ref "IC24") (pin "10") (pinfunction "3B_10") (pintype "input"))
    )
    (net (code "358") (name "unconnected-(IC24A-3Y-Pad9)") (class "Default")
      (node (ref "IC24") (pin "9") (pinfunction "3Y_9") (pintype "output"))
    )
    (net (code "359") (name "unconnected-(IC24A-4A-Pad14)") (class "Default")
      (node (ref "IC24") (pin "14") (pinfunction "4A_14") (pintype "input"))
    )
    (net (code "360") (name "unconnected-(IC24A-4B-Pad13)") (class "Default")
      (node (ref "IC24") (pin "13") (pinfunction "4B_13") (pintype "input"))
    )
    (net (code "361") (name "unconnected-(IC24A-4Y-Pad12)") (class "Default")
      (node (ref "IC24") (pin "12") (pinfunction "4Y_12") (pintype "output"))
    )
    (net (code "362") (name "unconnected-(IC24A-G-Pad15)") (class "Default")
      (node (ref "IC24") (pin "15") (pinfunction "G_15") (pintype "input"))
    )
    (net (code "363") (name "unconnected-(IC24A-~{A}{slash}B-Pad1)") (class "Default")
      (node (ref "IC24") (pin "1") (pinfunction "~{A}/B_1") (pintype "input"))
    )
    (net (code "364") (name "unconnected-(U$1-PadICSP1)") (class "Default")
      (node (ref "U$1") (pin "ICSP1") (pinfunction "ICSP1_ICSP1") (pintype "bidirectional"))
    )
    (net (code "365") (name "unconnected-(U$1-PadICSP2)") (class "Default")
      (node (ref "U$1") (pin "ICSP2") (pinfunction "ICSP2_ICSP2") (pintype "bidirectional"))
    )
    (net (code "366") (name "unconnected-(U$1-PadICSP3)") (class "Default")
      (node (ref "U$1") (pin "ICSP3") (pinfunction "ICSP3_ICSP3") (pintype "bidirectional"))
    )
    (net (code "367") (name "unconnected-(U$1-PadICSP4)") (class "Default")
      (node (ref "U$1") (pin "ICSP4") (pinfunction "ICSP4_ICSP4") (pintype "bidirectional"))
    )
    (net (code "368") (name "unconnected-(U$1-PadICSP5)") (class "Default")
      (node (ref "U$1") (pin "ICSP5") (pinfunction "ICSP5_ICSP5") (pintype "bidirectional"))
    )
    (net (code "369") (name "unconnected-(U$1-PadICSP6)") (class "Default")
      (node (ref "U$1") (pin "ICSP6") (pinfunction "ICSP6_ICSP6") (pintype "bidirectional"))
    )
  )
)
